# Singularitron_1B.net
KiCad netlist of a schematic drawn in EAGLE
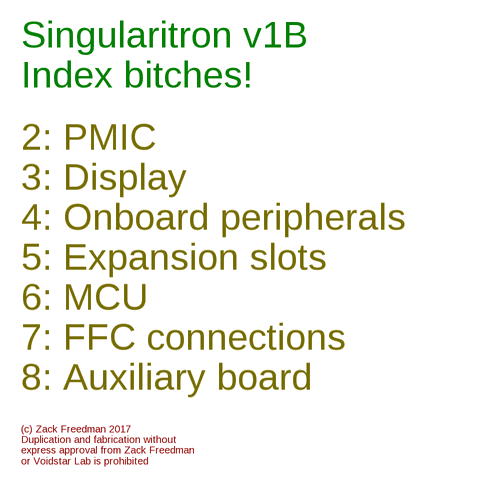
[diagram p0: schematic, sheet 1]
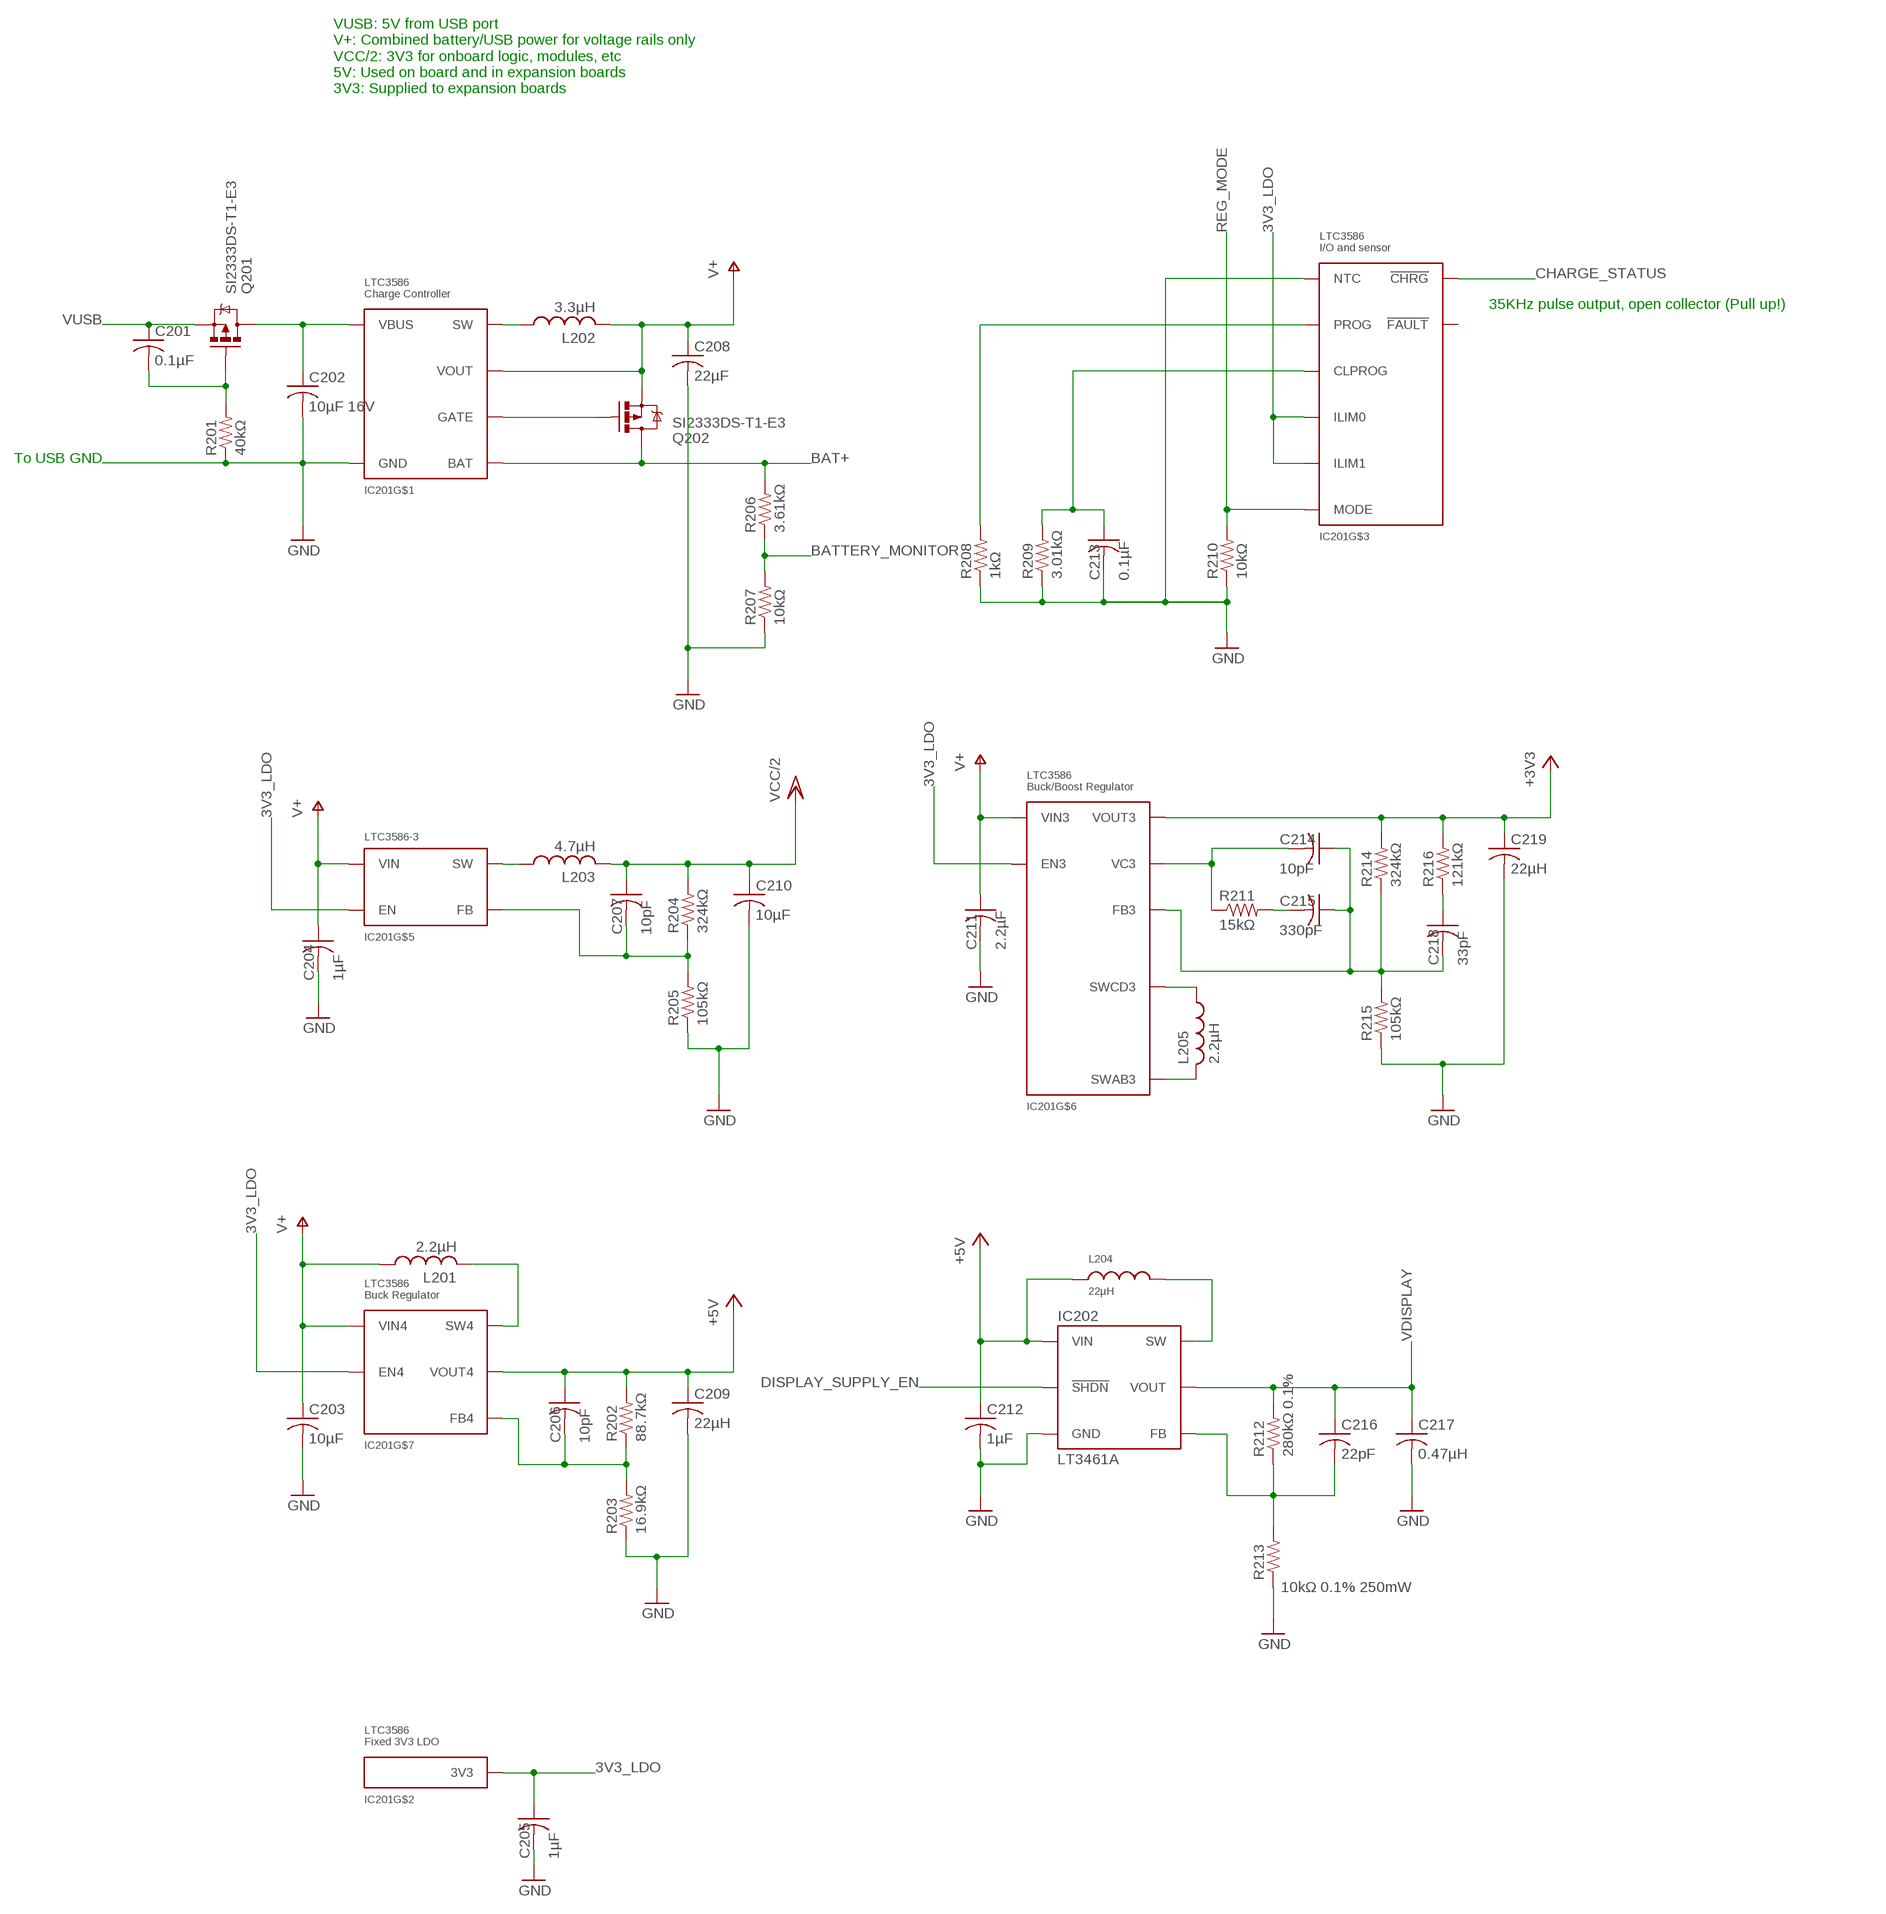
[diagram p1: schematic, sheet 2]
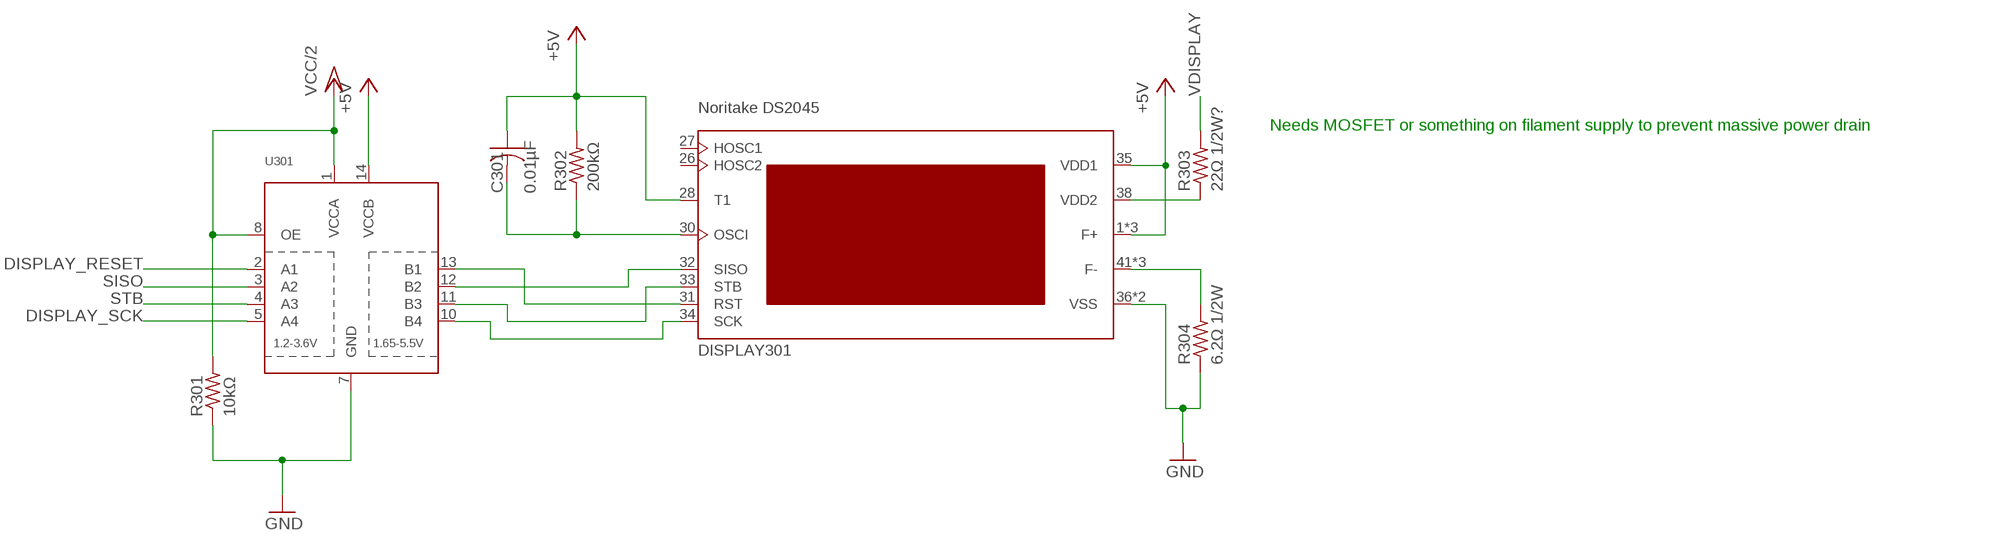
[diagram p2: schematic, sheet 3]
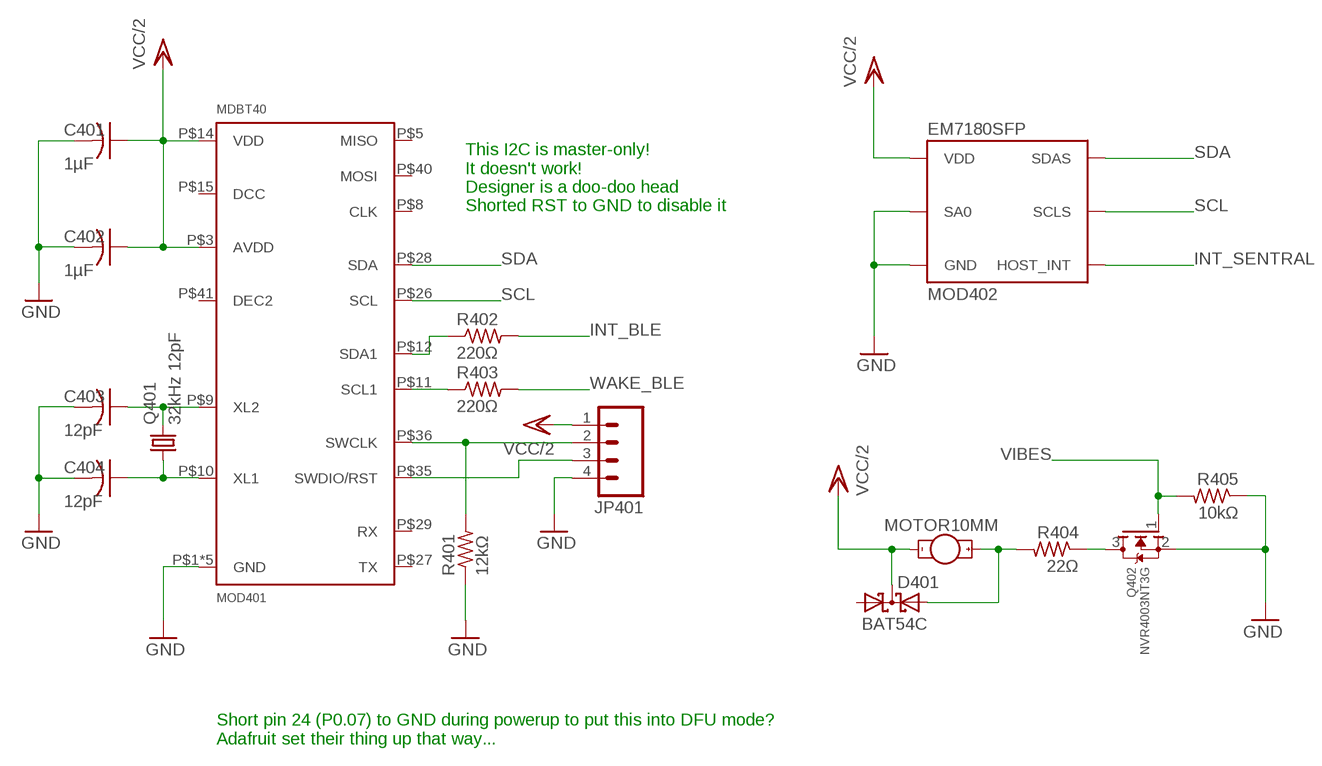
[diagram p3: schematic, sheet 4]
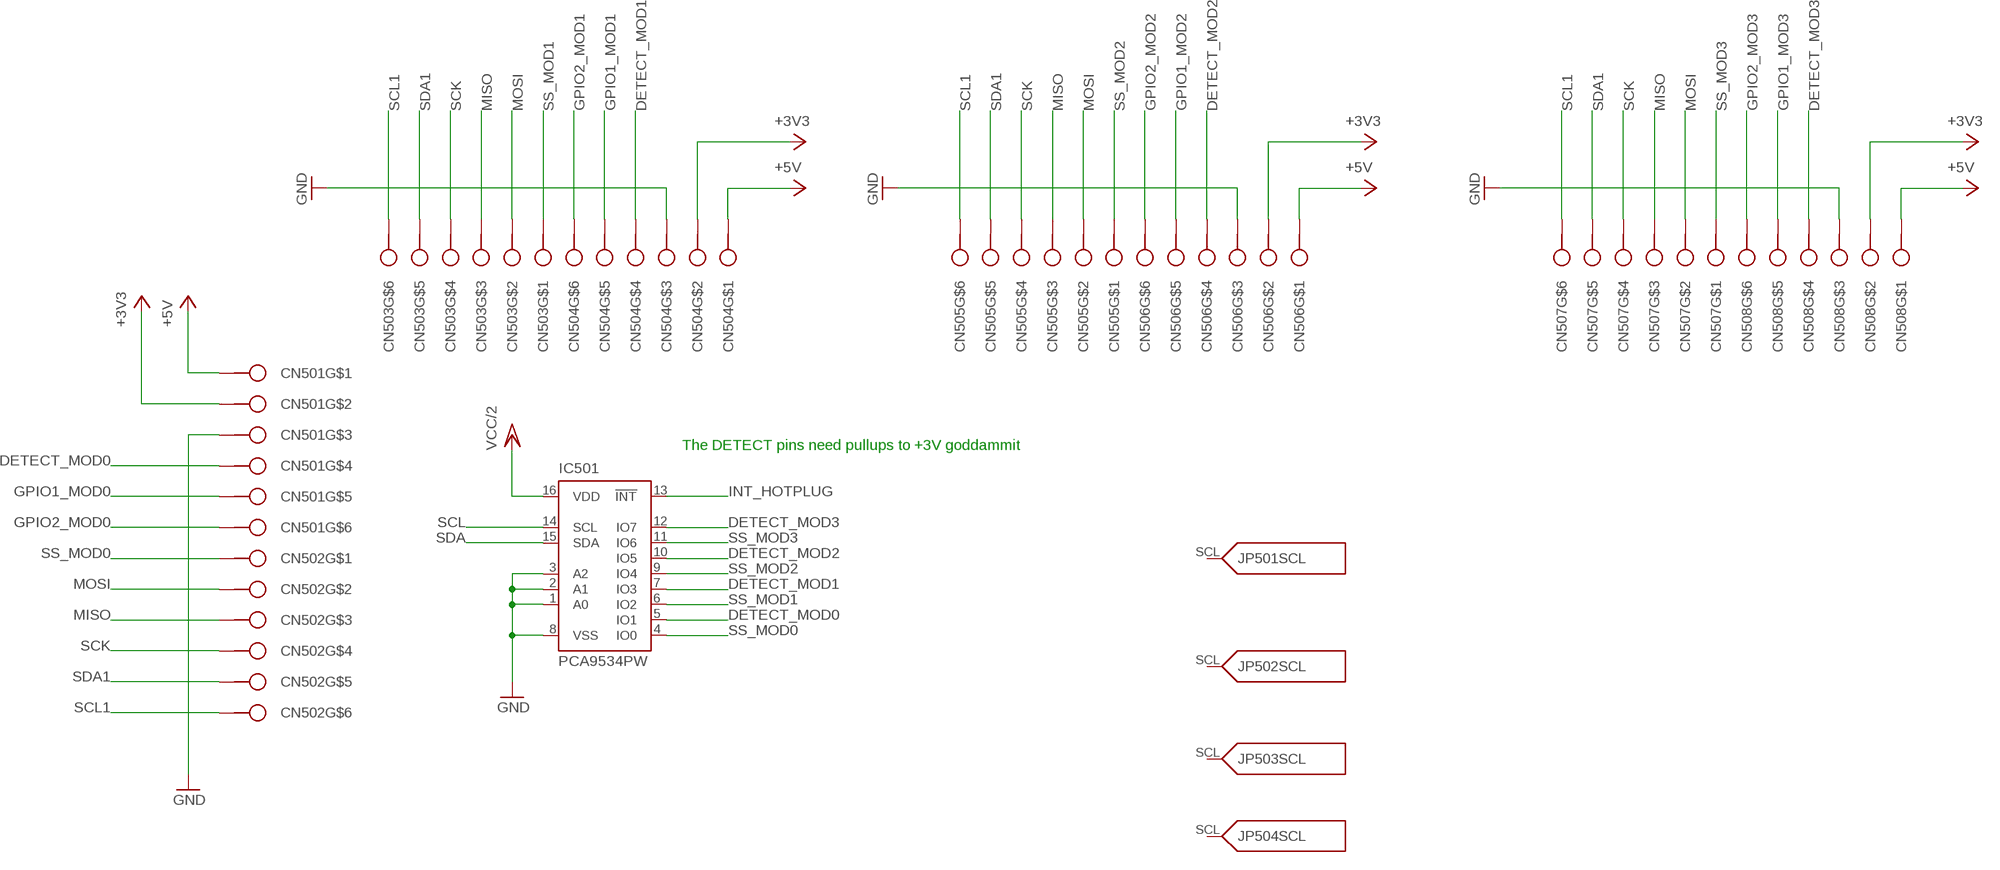
[diagram p4: schematic, sheet 5]
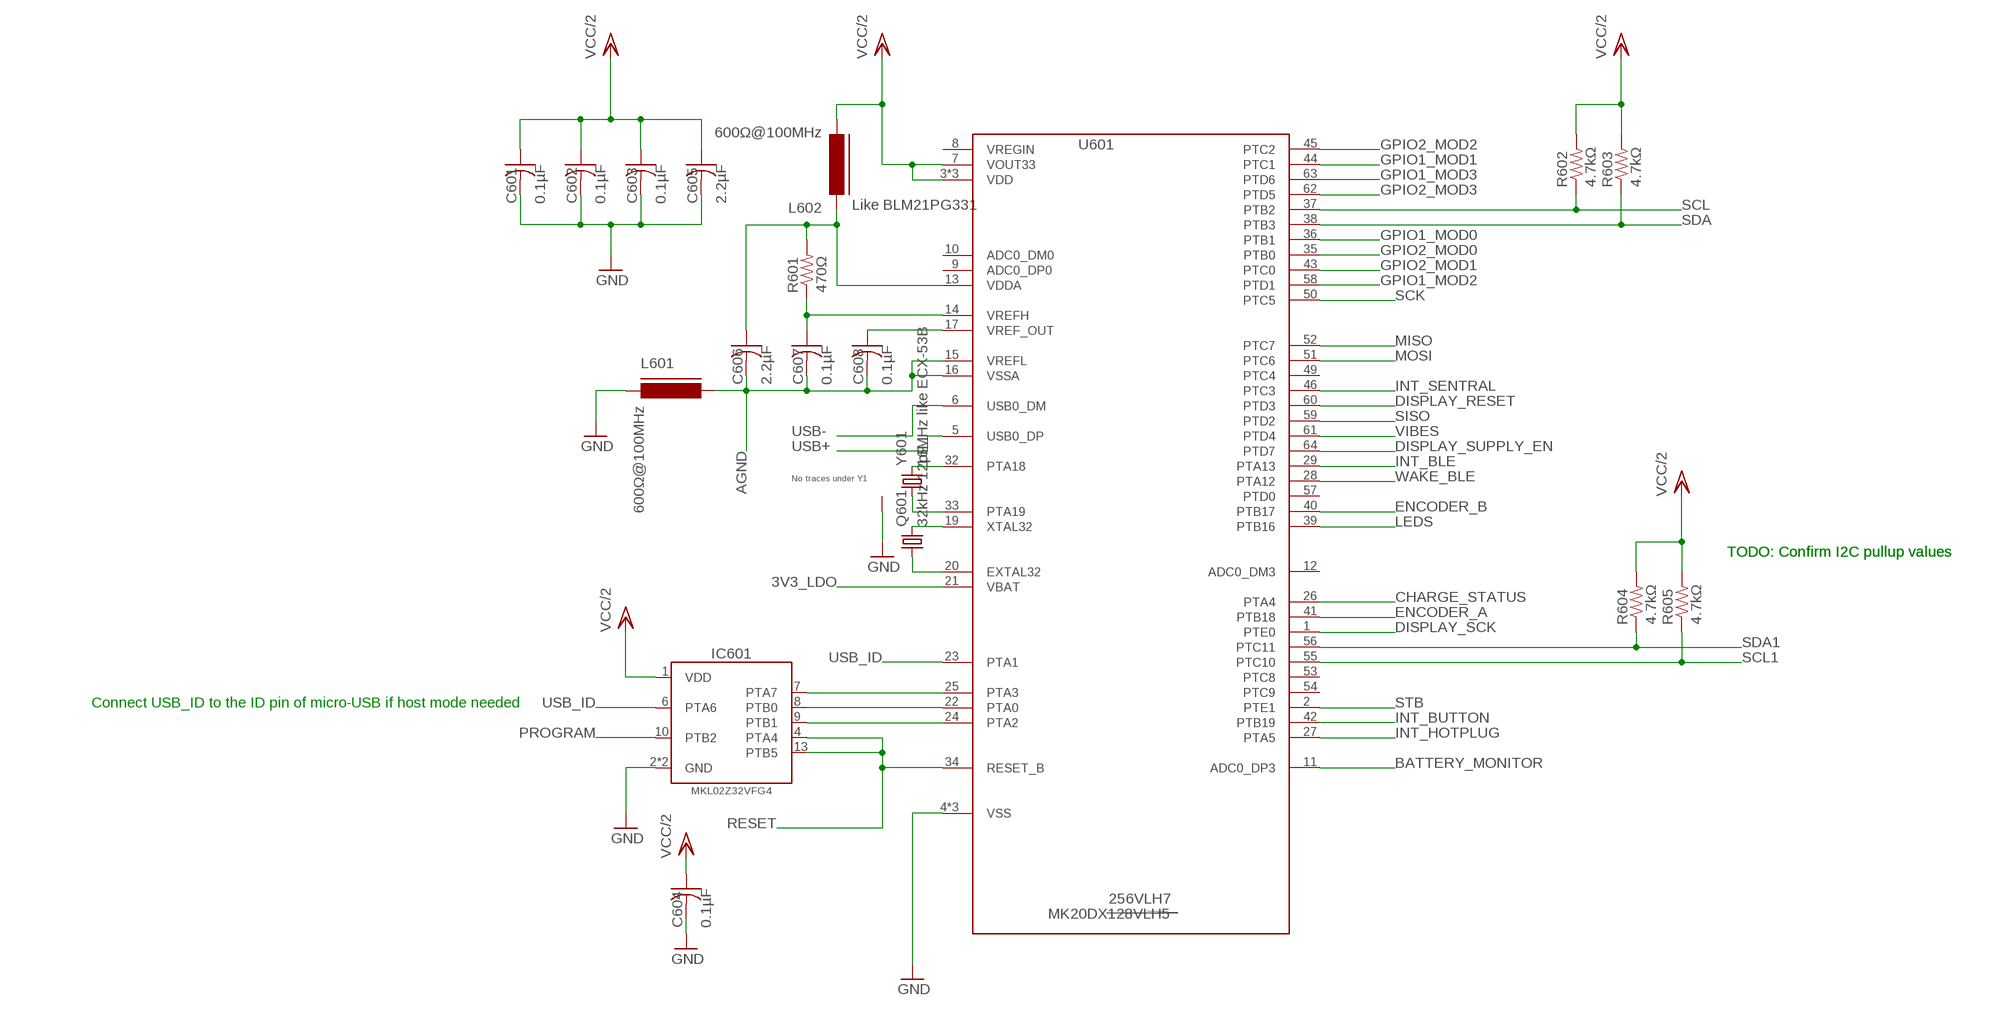
[diagram p5: schematic, sheet 6]
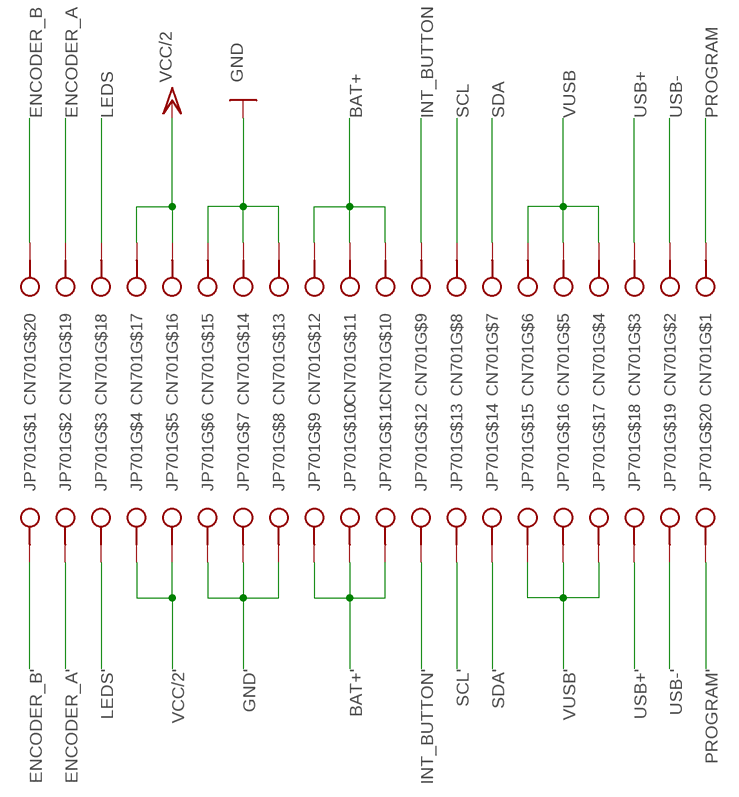
[diagram p6: schematic, sheet 7]
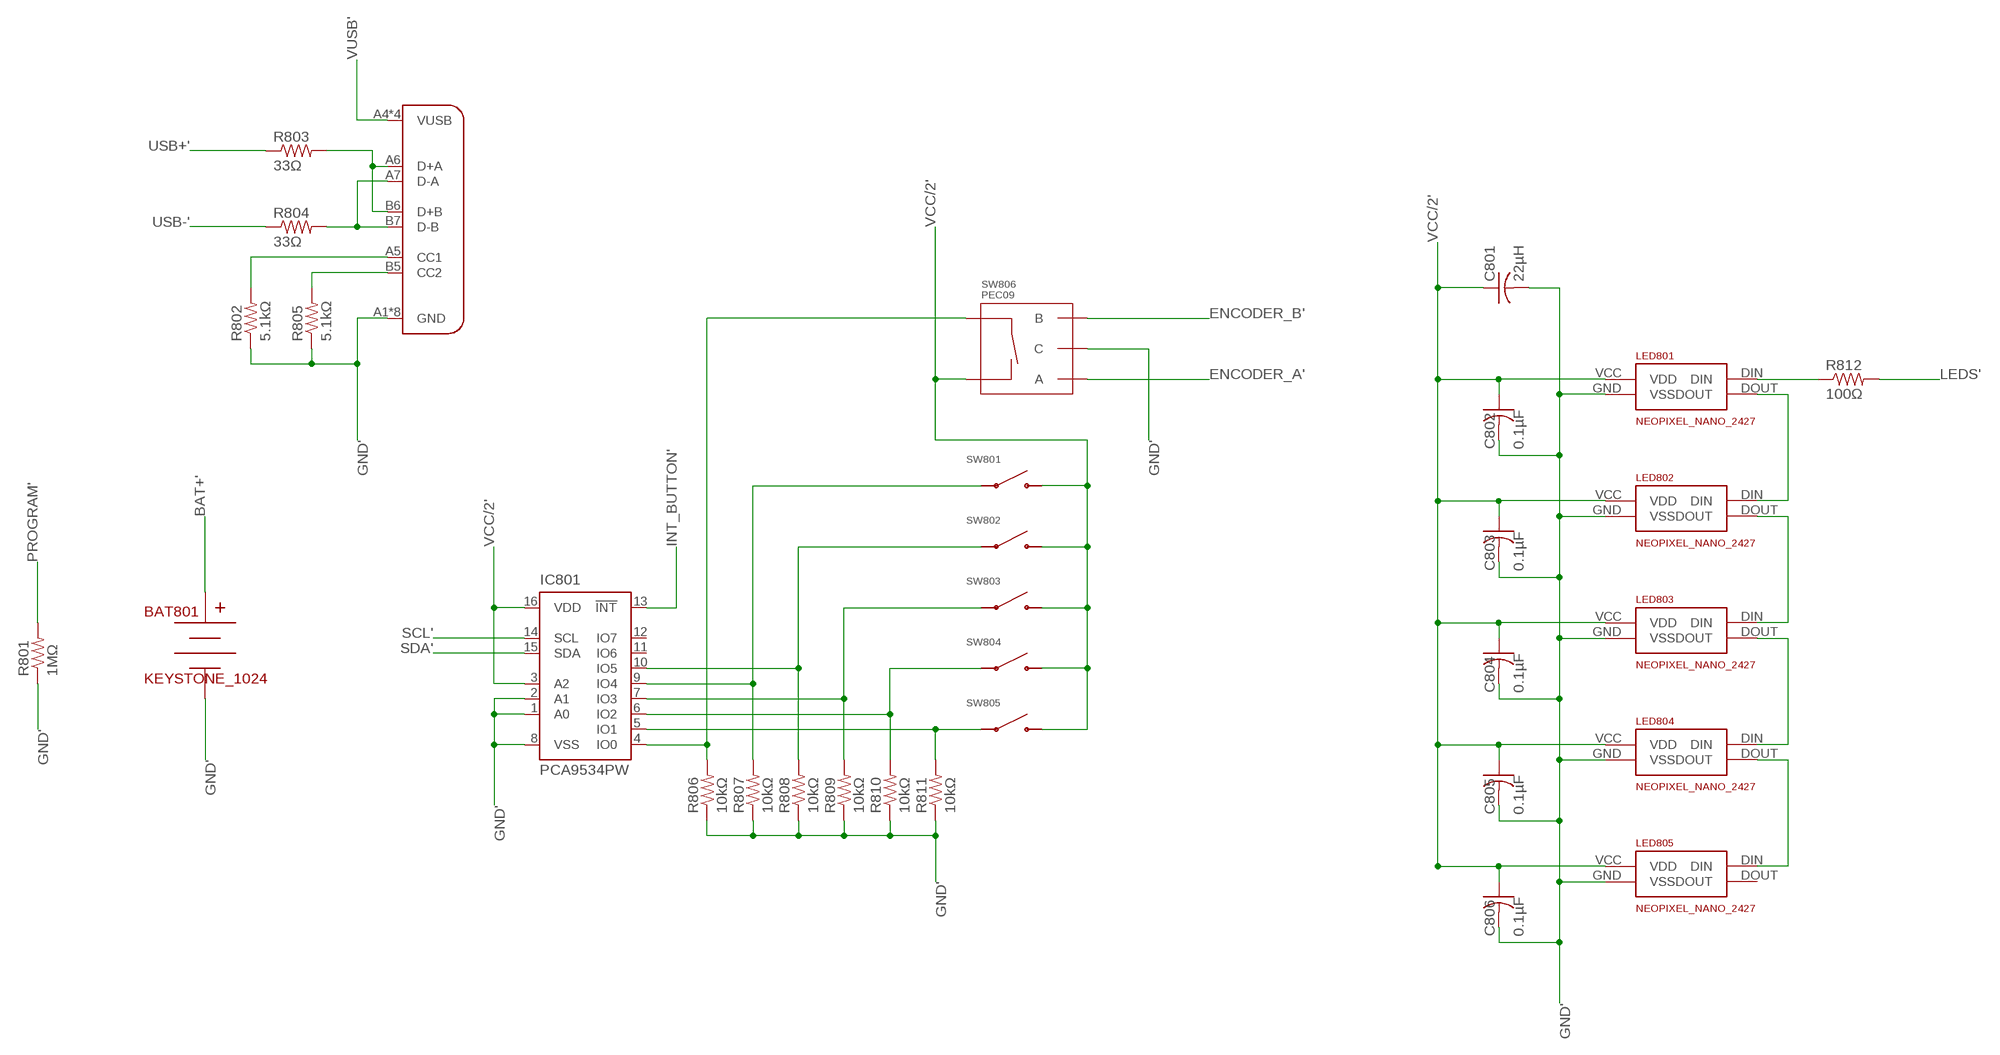
[diagram p7: schematic, sheet 8]

(export (version "E")
  (design (tool "Eeschema 10.0.6"))
  (components
    (comp (ref "C201")
      (value "0.1µF")
      (footprint "eagle-import:C0603")
      (libsource (lib "eagle-import") (part "C-USC0603"))
    )
    (comp (ref "C202")
      (value "10µF 16V")
      (footprint "eagle-import:C0805")
      (libsource (lib "eagle-import") (part "C-USC0805"))
    )
    (comp (ref "C203")
      (value "10µF")
      (footprint "eagle-import:C0805")
      (libsource (lib "eagle-import") (part "C-USC0805"))
    )
    (comp (ref "C204")
      (value "1µF")
      (footprint "eagle-import:C0603")
      (libsource (lib "eagle-import") (part "C-USC0603"))
    )
    (comp (ref "C205")
      (value "1µF")
      (footprint "eagle-import:C0603")
      (libsource (lib "eagle-import") (part "C-USC0603"))
    )
    (comp (ref "C206")
      (value "10pF")
      (footprint "eagle-import:C0603")
      (libsource (lib "eagle-import") (part "C-USC0603"))
    )
    (comp (ref "C207")
      (value "10pF")
      (footprint "eagle-import:C0603")
      (libsource (lib "eagle-import") (part "C-USC0603"))
    )
    (comp (ref "C208")
      (value "22µF")
      (footprint "eagle-import:C1210")
      (libsource (lib "eagle-import") (part "C-USC1210"))
    )
    (comp (ref "C209")
      (value "22µH")
      (footprint "eagle-import:C1210")
      (libsource (lib "eagle-import") (part "C-USC1210"))
    )
    (comp (ref "C210")
      (value "10µF")
      (footprint "eagle-import:C0805")
      (libsource (lib "eagle-import") (part "C-USC0805"))
    )
    (comp (ref "C211")
      (value "2.2µF")
      (footprint "eagle-import:C0603")
      (libsource (lib "eagle-import") (part "C-USC0603"))
    )
    (comp (ref "C212")
      (value "1µF")
      (footprint "eagle-import:C0805")
      (libsource (lib "eagle-import") (part "C-USC0805"))
    )
    (comp (ref "C213")
      (value "0.1µF")
      (footprint "eagle-import:C0603")
      (libsource (lib "eagle-import") (part "C-USC0603"))
    )
    (comp (ref "C214")
      (value "10pF")
      (footprint "eagle-import:C0603")
      (libsource (lib "eagle-import") (part "C-USC0603"))
    )
    (comp (ref "C215")
      (value "330pF")
      (footprint "eagle-import:C0603")
      (libsource (lib "eagle-import") (part "C-USC0603"))
    )
    (comp (ref "C216")
      (value "22pF")
      (footprint "eagle-import:C0805")
      (libsource (lib "eagle-import") (part "C-USC0805"))
    )
    (comp (ref "C217")
      (value "0.47µH")
      (footprint "eagle-import:C1210")
      (libsource (lib "eagle-import") (part "C-USC1210"))
    )
    (comp (ref "C218")
      (value "33pF")
      (footprint "eagle-import:C0603")
      (libsource (lib "eagle-import") (part "C-USC0603"))
    )
    (comp (ref "C219")
      (value "22µH")
      (footprint "eagle-import:C1210")
      (libsource (lib "eagle-import") (part "C-USC1210"))
    )
    (comp (ref "IC201")
      (value "LTC3586-3")
      (footprint "eagle-import:QFN-38_EP_UFE")
      (libsource (lib "eagle-import") (part "LTC3586-3"))
    )
    (comp (ref "IC202")
      (value "LT3461A")
      (footprint "eagle-import:SOT-23")
      (libsource (lib "eagle-import") (part "LT3461A"))
    )
    (comp (ref "L201")
      (value "2.2µH")
      (footprint "eagle-import:CDRH4D22_HP")
      (libsource (lib "eagle-import") (part "CDRH4D22/HP"))
    )
    (comp (ref "L202")
      (value "3.3µH")
      (footprint "eagle-import:CDRH6D12")
      (libsource (lib "eagle-import") (part "CDRH6D12"))
    )
    (comp (ref "L203")
      (value "4.7µH")
      (footprint "eagle-import:CDRH3D16_HP")
      (libsource (lib "eagle-import") (part "CDRH3D16/HP"))
    )
    (comp (ref "L204")
      (value "22µH")
      (footprint "eagle-import:CDPH4D19F")
      (libsource (lib "eagle-import") (part "SUMIDA_CDPH4D19F"))
    )
    (comp (ref "L205")
      (value "2.2µH")
      (footprint "eagle-import:CDRH4D22_HP")
      (libsource (lib "eagle-import") (part "CDRH4D22/HP"))
    )
    (comp (ref "Q201")
      (value "SI2333DS-T1-E3")
      (footprint "eagle-import:SOT23-3")
      (libsource (lib "eagle-import") (part "MOSFET-PCHANNELSMD"))
    )
    (comp (ref "Q202")
      (value "SI2333DS-T1-E3")
      (footprint "eagle-import:SOT23-3")
      (libsource (lib "eagle-import") (part "MOSFET-PCHANNELSMD"))
    )
    (comp (ref "R201")
      (value "40kΩ")
      (footprint "eagle-import:R0603")
      (libsource (lib "eagle-import") (part "R-US_R0603"))
    )
    (comp (ref "R202")
      (value "88.7kΩ")
      (footprint "eagle-import:R0603")
      (libsource (lib "eagle-import") (part "R-US_R0603"))
    )
    (comp (ref "R203")
      (value "16.9kΩ")
      (footprint "eagle-import:R0603")
      (libsource (lib "eagle-import") (part "R-US_R0603"))
    )
    (comp (ref "R204")
      (value "324kΩ")
      (footprint "eagle-import:R0603")
      (libsource (lib "eagle-import") (part "R-US_R0603"))
    )
    (comp (ref "R205")
      (value "105kΩ")
      (footprint "eagle-import:R0603")
      (libsource (lib "eagle-import") (part "R-US_R0603"))
    )
    (comp (ref "R206")
      (value "3.61kΩ")
      (footprint "eagle-import:R0603")
      (libsource (lib "eagle-import") (part "R-US_R0603"))
    )
    (comp (ref "R207")
      (value "10kΩ")
      (footprint "eagle-import:R0603")
      (libsource (lib "eagle-import") (part "R-US_R0603"))
    )
    (comp (ref "R208")
      (value "1kΩ")
      (footprint "eagle-import:R0603")
      (libsource (lib "eagle-import") (part "R-US_R0603"))
    )
    (comp (ref "R209")
      (value "3.01kΩ")
      (footprint "eagle-import:R0603")
      (libsource (lib "eagle-import") (part "R-US_R0603"))
    )
    (comp (ref "R210")
      (value "10kΩ")
      (footprint "eagle-import:R0603")
      (libsource (lib "eagle-import") (part "R-US_R0603"))
    )
    (comp (ref "R211")
      (value "15kΩ")
      (footprint "eagle-import:R0603")
      (libsource (lib "eagle-import") (part "R-US_R0603"))
    )
    (comp (ref "R212")
      (value "280kΩ 0.1%")
      (footprint "eagle-import:R0603")
      (libsource (lib "eagle-import") (part "R-US_R0603"))
    )
    (comp (ref "R213")
      (value "10kΩ 0.1% 250mW")
      (footprint "eagle-import:R0805")
      (libsource (lib "eagle-import") (part "R-US_R0805"))
    )
    (comp (ref "R214")
      (value "324kΩ")
      (footprint "eagle-import:R0603")
      (libsource (lib "eagle-import") (part "R-US_R0603"))
    )
    (comp (ref "R215")
      (value "105kΩ")
      (footprint "eagle-import:R0603")
      (libsource (lib "eagle-import") (part "R-US_R0603"))
    )
    (comp (ref "R216")
      (value "121kΩ")
      (footprint "eagle-import:R0603")
      (libsource (lib "eagle-import") (part "R-US_R0603"))
    )
    (comp (ref "C601")
      (value "0.1µF")
      (footprint "eagle-import:C0603")
      (libsource (lib "eagle-import") (part "C-USC0603"))
    )
    (comp (ref "C602")
      (value "0.1µF")
      (footprint "eagle-import:C0603")
      (libsource (lib "eagle-import") (part "C-USC0603"))
    )
    (comp (ref "C603")
      (value "0.1µF")
      (footprint "eagle-import:C0603")
      (libsource (lib "eagle-import") (part "C-USC0603"))
    )
    (comp (ref "C604")
      (value "0.1µF")
      (footprint "eagle-import:C0603")
      (libsource (lib "eagle-import") (part "C-USC0603"))
    )
    (comp (ref "C605")
      (value "2.2µF")
      (footprint "eagle-import:C0603")
      (libsource (lib "eagle-import") (part "C-USC0603"))
    )
    (comp (ref "C606")
      (value "2.2µF")
      (footprint "eagle-import:C0603")
      (libsource (lib "eagle-import") (part "C-USC0603"))
    )
    (comp (ref "C607")
      (value "0.1µF")
      (footprint "eagle-import:C0603")
      (libsource (lib "eagle-import") (part "C-USC0603"))
    )
    (comp (ref "C608")
      (value "0.1µF")
      (footprint "eagle-import:C0603")
      (libsource (lib "eagle-import") (part "C-USC0603"))
    )
    (comp (ref "IC601")
      (value "MKL02Z32VFG4")
      (footprint "eagle-import:QFN16-3X3")
      (libsource (lib "eagle-import") (part "MKL02Z32VFG4"))
    )
    (comp (ref "L601")
      (value "600Ω@100MHz")
      (footprint "eagle-import:FB603")
      (libsource (lib "eagle-import") (part "FERRITE-0603"))
    )
    (comp (ref "L602")
      (value "600Ω@100MHz")
      (footprint "eagle-import:FB603")
      (libsource (lib "eagle-import") (part "FERRITE-0603"))
    )
    (comp (ref "Q601")
      (value "32kHz 12pF")
      (footprint "eagle-import:FC-12M")
      (libsource (lib "eagle-import") (part "FC-12M"))
    )
    (comp (ref "R601")
      (value "470Ω")
      (footprint "eagle-import:R0603")
      (libsource (lib "eagle-import") (part "R-US_R0603"))
    )
    (comp (ref "R602")
      (value "4.7kΩ")
      (footprint "eagle-import:R0603")
      (libsource (lib "eagle-import") (part "R-US_R0603"))
    )
    (comp (ref "R603")
      (value "4.7kΩ")
      (footprint "eagle-import:R0603")
      (libsource (lib "eagle-import") (part "R-US_R0603"))
    )
    (comp (ref "R604")
      (value "4.7kΩ")
      (footprint "eagle-import:R0603")
      (libsource (lib "eagle-import") (part "R-US_R0603"))
    )
    (comp (ref "R605")
      (value "4.7kΩ")
      (footprint "eagle-import:R0603")
      (libsource (lib "eagle-import") (part "R-US_R0603"))
    )
    (comp (ref "U601")
      (value "MK20DX128VLH5")
      (footprint "eagle-import:MK20DX128VLH5")
      (libsource (lib "eagle-import") (part "MK20DX128VLH5"))
    )
    (comp (ref "Y601")
      (value "16MHz like ECX-53B")
      (footprint "eagle-import:CRYSTAL-SMD-5X3")
      (libsource (lib "eagle-import") (part "CRYSTAL-SHIELDED"))
    )
    (comp (ref "CN701")
      (value "HFW20R-1ST")
      (footprint "eagle-import:HFW20R-1STE1LF")
      (libsource (lib "eagle-import") (part "HFW20R-1ST"))
    )
    (comp (ref "JP701")
      (value "FFC_1MM_20POS_DIRECT")
      (footprint "eagle-import:FFC_1MM_20POS_DIRECT")
      (libsource (lib "eagle-import") (part "FFC_1MM_20POS_DIRECT"))
    )
    (comp (ref "C401")
      (value "1µF")
      (footprint "eagle-import:C0603")
      (libsource (lib "eagle-import") (part "C-USC0603"))
    )
    (comp (ref "C402")
      (value "1µF")
      (footprint "eagle-import:C0603")
      (libsource (lib "eagle-import") (part "C-USC0603"))
    )
    (comp (ref "C403")
      (value "12pF")
      (footprint "eagle-import:C0603")
      (libsource (lib "eagle-import") (part "C-USC0603"))
    )
    (comp (ref "C404")
      (value "12pF")
      (footprint "eagle-import:C0603")
      (libsource (lib "eagle-import") (part "C-USC0603"))
    )
    (comp (ref "D401")
      (value "BAT54C")
      (footprint "eagle-import:SOT23")
      (libsource (lib "eagle-import") (part "BAT54C"))
    )
    (comp (ref "JP401")
      (value "M041.27MM")
      (footprint "eagle-import:1X04-1.27MM")
      (libsource (lib "eagle-import") (part "M041.27MM"))
    )
    (comp (ref "MOD401")
      (value "MDBT40")
      (footprint "eagle-import:MDBT40")
      (libsource (lib "eagle-import") (part "MDBT40"))
    )
    (comp (ref "MOD402")
      (value "EM7180SFP")
      (footprint "eagle-import:EM7180SFP")
      (libsource (lib "eagle-import") (part "EM7180SFP"))
    )
    (comp (ref "MOTOR401")
      (value "MOTOR10MM")
      (footprint "eagle-import:VIBE-MOTOR-10MM")
      (libsource (lib "eagle-import") (part "MOTOR10MM"))
    )
    (comp (ref "Q401")
      (value "32kHz 12pF")
      (footprint "eagle-import:FC-12M")
      (libsource (lib "eagle-import") (part "FC-12M"))
    )
    (comp (ref "Q402")
      (value "NVR4003NT3G")
      (footprint "eagle-import:SOT23")
      (libsource (lib "eagle-import") (part "MOSFET-NREFLOW"))
    )
    (comp (ref "R401")
      (value "12kΩ")
      (footprint "eagle-import:R0603")
      (libsource (lib "eagle-import") (part "R-US_R0603"))
    )
    (comp (ref "R402")
      (value "220Ω")
      (footprint "eagle-import:R0603")
      (libsource (lib "eagle-import") (part "R-US_R0603"))
    )
    (comp (ref "R403")
      (value "220Ω")
      (footprint "eagle-import:R0603")
      (libsource (lib "eagle-import") (part "R-US_R0603"))
    )
    (comp (ref "R404")
      (value "22Ω")
      (footprint "eagle-import:R0603")
      (libsource (lib "eagle-import") (part "R-US_R0603"))
    )
    (comp (ref "R405")
      (value "10kΩ")
      (footprint "eagle-import:R0603")
      (libsource (lib "eagle-import") (part "R-US_R0603"))
    )
    (comp (ref "CN501")
      (value "AVX_9155066")
      (footprint "eagle-import:9155006")
      (libsource (lib "eagle-import") (part "AVX_9155066"))
    )
    (comp (ref "CN502")
      (value "AVX_9155066")
      (footprint "eagle-import:9155006")
      (libsource (lib "eagle-import") (part "AVX_9155066"))
    )
    (comp (ref "CN503")
      (value "AVX_9155066")
      (footprint "eagle-import:9155006")
      (libsource (lib "eagle-import") (part "AVX_9155066"))
    )
    (comp (ref "CN504")
      (value "AVX_9155066")
      (footprint "eagle-import:9155006")
      (libsource (lib "eagle-import") (part "AVX_9155066"))
    )
    (comp (ref "CN505")
      (value "AVX_9155066")
      (footprint "eagle-import:9155006")
      (libsource (lib "eagle-import") (part "AVX_9155066"))
    )
    (comp (ref "CN506")
      (value "AVX_9155066")
      (footprint "eagle-import:9155006")
      (libsource (lib "eagle-import") (part "AVX_9155066"))
    )
    (comp (ref "CN507")
      (value "AVX_9155066")
      (footprint "eagle-import:9155006")
      (libsource (lib "eagle-import") (part "AVX_9155066"))
    )
    (comp (ref "CN508")
      (value "AVX_9155066")
      (footprint "eagle-import:9155006")
      (libsource (lib "eagle-import") (part "AVX_9155066"))
    )
    (comp (ref "IC501")
      (value "PCA9534PW")
      (footprint "eagle-import:TSSOP16")
      (libsource (lib "eagle-import") (part "PCA9534PW"))
    )
    (comp (ref "JP501")
      (value "SINGULARITRON_CART_BASE")
      (footprint "eagle-import:SINGULARITRON_CART_BASE")
      (libsource (lib "eagle-import") (part "SINGULARITRON_CART_BASE"))
    )
    (comp (ref "JP502")
      (value "SINGULARITRON_CART_BASE")
      (footprint "eagle-import:SINGULARITRON_CART_BASE")
      (libsource (lib "eagle-import") (part "SINGULARITRON_CART_BASE"))
    )
    (comp (ref "JP503")
      (value "SINGULARITRON_CART_BASE")
      (footprint "eagle-import:SINGULARITRON_CART_BASE")
      (libsource (lib "eagle-import") (part "SINGULARITRON_CART_BASE"))
    )
    (comp (ref "JP504")
      (value "SINGULARITRON_CART_BASE")
      (footprint "eagle-import:SINGULARITRON_CART_BASE")
      (libsource (lib "eagle-import") (part "SINGULARITRON_CART_BASE"))
    )
    (comp (ref "C301")
      (value "0.01µF")
      (footprint "eagle-import:C0603")
      (libsource (lib "eagle-import") (part "C-USC0603"))
    )
    (comp (ref "DISPLAY301")
      (value "DS2045")
      (footprint "eagle-import:DS2045")
      (libsource (lib "eagle-import") (part "DS2045"))
    )
    (comp (ref "R301")
      (value "10kΩ")
      (footprint "eagle-import:R0603")
      (libsource (lib "eagle-import") (part "R-US_R0603"))
    )
    (comp (ref "R302")
      (value "200kΩ")
      (footprint "eagle-import:R0603")
      (libsource (lib "eagle-import") (part "R-US_R0603"))
    )
    (comp (ref "R303")
      (value "22Ω 1/2W?")
      (footprint "eagle-import:R0805")
      (libsource (lib "eagle-import") (part "R-US_R0805"))
    )
    (comp (ref "R304")
      (value "6.2Ω 1/2W")
      (footprint "eagle-import:R0805")
      (libsource (lib "eagle-import") (part "R-US_R0805"))
    )
    (comp (ref "U301")
      (value "TXB0104PWR")
      (footprint "eagle-import:TSSOP14")
      (libsource (lib "eagle-import") (part "TXB0104PWR"))
    )
    (comp (ref "BAT801")
      (value "KEYSTONE_1024")
      (footprint "eagle-import:KEYSTONE-1024-PROVISIONAL")
      (libsource (lib "eagle-import") (part "KEYSTONE_1024"))
    )
    (comp (ref "C801")
      (value "22µH")
      (footprint "eagle-import:C1210")
      (libsource (lib "eagle-import") (part "C-USC1210"))
    )
    (comp (ref "C802")
      (value "0.1µF")
      (footprint "eagle-import:C0603")
      (libsource (lib "eagle-import") (part "C-USC0603"))
    )
    (comp (ref "C803")
      (value "0.1µF")
      (footprint "eagle-import:C0603")
      (libsource (lib "eagle-import") (part "C-USC0603"))
    )
    (comp (ref "C804")
      (value "0.1µF")
      (footprint "eagle-import:C0603")
      (libsource (lib "eagle-import") (part "C-USC0603"))
    )
    (comp (ref "C805")
      (value "0.1µF")
      (footprint "eagle-import:C0603")
      (libsource (lib "eagle-import") (part "C-USC0603"))
    )
    (comp (ref "C806")
      (value "0.1µF")
      (footprint "eagle-import:C0603")
      (libsource (lib "eagle-import") (part "C-USC0603"))
    )
    (comp (ref "CN801")
      (value "12401548E4#2A")
      (footprint "eagle-import:12401548E4#2A")
      (libsource (lib "eagle-import") (part "12401548E4#2A"))
    )
    (comp (ref "IC801")
      (value "PCA9534PW")
      (footprint "eagle-import:TSSOP16")
      (libsource (lib "eagle-import") (part "PCA9534PW"))
    )
    (comp (ref "LED801")
      (value "NEOPIXEL_NANO_2427")
      (footprint "eagle-import:SK6805-2427")
      (libsource (lib "eagle-import") (part "NEOPIXEL_NANO_2427"))
    )
    (comp (ref "LED802")
      (value "NEOPIXEL_NANO_2427")
      (footprint "eagle-import:SK6805-2427")
      (libsource (lib "eagle-import") (part "NEOPIXEL_NANO_2427"))
    )
    (comp (ref "LED803")
      (value "NEOPIXEL_NANO_2427")
      (footprint "eagle-import:SK6805-2427")
      (libsource (lib "eagle-import") (part "NEOPIXEL_NANO_2427"))
    )
    (comp (ref "LED804")
      (value "NEOPIXEL_NANO_2427")
      (footprint "eagle-import:SK6805-2427")
      (libsource (lib "eagle-import") (part "NEOPIXEL_NANO_2427"))
    )
    (comp (ref "LED805")
      (value "NEOPIXEL_NANO_2427")
      (footprint "eagle-import:SK6805-2427")
      (libsource (lib "eagle-import") (part "NEOPIXEL_NANO_2427"))
    )
    (comp (ref "R801")
      (value "1MΩ")
      (footprint "eagle-import:R0603")
      (libsource (lib "eagle-import") (part "R-US_R0603"))
    )
    (comp (ref "R802")
      (value "5.1kΩ")
      (footprint "eagle-import:R0603")
      (libsource (lib "eagle-import") (part "R-US_R0603"))
    )
    (comp (ref "R803")
      (value "33Ω")
      (footprint "eagle-import:R0603")
      (libsource (lib "eagle-import") (part "R-US_R0603"))
    )
    (comp (ref "R804")
      (value "33Ω")
      (footprint "eagle-import:R0603")
      (libsource (lib "eagle-import") (part "R-US_R0603"))
    )
    (comp (ref "R805")
      (value "5.1kΩ")
      (footprint "eagle-import:R0603")
      (libsource (lib "eagle-import") (part "R-US_R0603"))
    )
    (comp (ref "R806")
      (value "10kΩ")
      (footprint "eagle-import:R0603")
      (libsource (lib "eagle-import") (part "R-US_R0603"))
    )
    (comp (ref "R807")
      (value "10kΩ")
      (footprint "eagle-import:R0603")
      (libsource (lib "eagle-import") (part "R-US_R0603"))
    )
    (comp (ref "R808")
      (value "10kΩ")
      (footprint "eagle-import:R0603")
      (libsource (lib "eagle-import") (part "R-US_R0603"))
    )
    (comp (ref "R809")
      (value "10kΩ")
      (footprint "eagle-import:R0603")
      (libsource (lib "eagle-import") (part "R-US_R0603"))
    )
    (comp (ref "R810")
      (value "10kΩ")
      (footprint "eagle-import:R0603")
      (libsource (lib "eagle-import") (part "R-US_R0603"))
    )
    (comp (ref "R811")
      (value "10kΩ")
      (footprint "eagle-import:R0603")
      (libsource (lib "eagle-import") (part "R-US_R0603"))
    )
    (comp (ref "R812")
      (value "100Ω")
      (footprint "eagle-import:R0603")
      (libsource (lib "eagle-import") (part "R-US_R0603"))
    )
    (comp (ref "SW801")
      (value "TACTILE_SWITCHTL3301-G")
      (footprint "eagle-import:TL3301-X-FXXX-X-G")
      (libsource (lib "eagle-import") (part "TACTILE_SWITCHTL3301-G"))
    )
    (comp (ref "SW802")
      (value "TACTILE_SWITCHTL3301-G")
      (footprint "eagle-import:TL3301-X-FXXX-X-G")
      (libsource (lib "eagle-import") (part "TACTILE_SWITCHTL3301-G"))
    )
    (comp (ref "SW803")
      (value "TACTILE_SWITCHTL3301-G")
      (footprint "eagle-import:TL3301-X-FXXX-X-G")
      (libsource (lib "eagle-import") (part "TACTILE_SWITCHTL3301-G"))
    )
    (comp (ref "SW804")
      (value "TACTILE_SWITCHTL3301-G")
      (footprint "eagle-import:TL3301-X-FXXX-X-G")
      (libsource (lib "eagle-import") (part "TACTILE_SWITCHTL3301-G"))
    )
    (comp (ref "SW805")
      (value "TACTILE_SWITCHTL3301-G")
      (footprint "eagle-import:TL3301-X-FXXX-X-G")
      (libsource (lib "eagle-import") (part "TACTILE_SWITCHTL3301-G"))
    )
    (comp (ref "SW806")
      (value "PEC09")
      (footprint "eagle-import:PEC09-2X20X-TXXXX")
      (libsource (lib "eagle-import") (part "PEC09"))
    )
  )
  (nets
    (net (code "1") (name "+3V3") (class "Default")
      (node (ref "C219") (pin "1") (pinfunction "1_1") (pintype "passive"))
      (node (ref "CN501") (pin "PAD2") (pinfunction "P$1_PAD2") (pintype "bidirectional"))
      (node (ref "CN504") (pin "PAD2") (pinfunction "P$1_PAD2") (pintype "bidirectional"))
      (node (ref "CN506") (pin "PAD2") (pinfunction "P$1_PAD2") (pintype "bidirectional"))
      (node (ref "CN508") (pin "PAD2") (pinfunction "P$1_PAD2") (pintype "bidirectional"))
      (node (ref "IC201") (pin "P$16") (pinfunction "VOUT3_P$16") (pintype "bidirectional"))
      (node (ref "IC201") (pin "P$17") (pinfunction "VOUT3_P$17") (pintype "bidirectional"))
      (node (ref "R214") (pin "2") (pinfunction "2_2") (pintype "passive"))
      (node (ref "R216") (pin "2") (pinfunction "2_2") (pintype "passive"))
    )
    (net (code "2") (name "+5V") (class "Default")
      (node (ref "C206") (pin "1") (pinfunction "1_1") (pintype "passive"))
      (node (ref "C209") (pin "1") (pinfunction "1_1") (pintype "passive"))
      (node (ref "C212") (pin "1") (pinfunction "1_1") (pintype "passive"))
      (node (ref "C301") (pin "1") (pinfunction "1_1") (pintype "passive"))
      (node (ref "CN501") (pin "PAD1") (pinfunction "P$1_PAD1") (pintype "bidirectional"))
      (node (ref "CN504") (pin "PAD1") (pinfunction "P$1_PAD1") (pintype "bidirectional"))
      (node (ref "CN506") (pin "PAD1") (pinfunction "P$1_PAD1") (pintype "bidirectional"))
      (node (ref "CN508") (pin "PAD1") (pinfunction "P$1_PAD1") (pintype "bidirectional"))
      (node (ref "DISPLAY301") (pin "1") (pinfunction "F+_1") (pintype "power_in"))
      (node (ref "DISPLAY301") (pin "2") (pinfunction "F+_2") (pintype "power_in"))
      (node (ref "DISPLAY301") (pin "28") (pinfunction "T1_28") (pintype "input"))
      (node (ref "DISPLAY301") (pin "3") (pinfunction "F+_3") (pintype "power_in"))
      (node (ref "DISPLAY301") (pin "35") (pinfunction "VDD1_35") (pintype "power_in"))
      (node (ref "IC201") (pin "P$6") (pinfunction "VOUT4_P$6") (pintype "bidirectional"))
      (node (ref "IC201") (pin "P$7") (pinfunction "VOUT4_P$7") (pintype "bidirectional"))
      (node (ref "IC202") (pin "P6") (pinfunction "VIN_P6") (pintype "bidirectional"))
      (node (ref "L204") (pin "P$1") (pinfunction "P$1_P$1") (pintype "bidirectional"))
      (node (ref "R202") (pin "2") (pinfunction "2_2") (pintype "passive"))
      (node (ref "R302") (pin "2") (pinfunction "2_2") (pintype "passive"))
      (node (ref "U301") (pin "14") (pinfunction "VCCB_14") (pintype "bidirectional"))
    )
    (net (code "3") (name "3V3_LDO") (class "Default")
      (node (ref "C205") (pin "1") (pinfunction "1_1") (pintype "passive"))
      (node (ref "IC201") (pin "P$1") (pinfunction "ILIM0_P$1") (pintype "bidirectional"))
      (node (ref "IC201") (pin "P$18") (pinfunction "EN3_P$18") (pintype "bidirectional"))
      (node (ref "IC201") (pin "P$2") (pinfunction "ILIM1_P$2") (pintype "bidirectional"))
      (node (ref "IC201") (pin "P$20") (pinfunction "EN_P$20") (pintype "bidirectional"))
      (node (ref "IC201") (pin "P$3") (pinfunction "3V3_P$3") (pintype "bidirectional"))
      (node (ref "IC201") (pin "P$33") (pinfunction "EN4_P$33") (pintype "bidirectional"))
      (node (ref "U601") (pin "21") (pinfunction "VBAT_21") (pintype "bidirectional"))
    )
    (net (code "4") (name "AGND") (class "Default")
      (node (ref "C606") (pin "2") (pinfunction "2_2") (pintype "passive"))
      (node (ref "C607") (pin "2") (pinfunction "2_2") (pintype "passive"))
      (node (ref "C608") (pin "2") (pinfunction "2_2") (pintype "passive"))
      (node (ref "L601") (pin "1") (pinfunction "1_1") (pintype "passive"))
      (node (ref "U601") (pin "15") (pinfunction "VREFL_15") (pintype "bidirectional"))
      (node (ref "U601") (pin "16") (pinfunction "VSSA_16") (pintype "bidirectional"))
    )
    (net (code "5") (name "BAT+") (class "Default")
      (node (ref "CN701") (pin "P$10") (pinfunction "P$1_P$10") (pintype "bidirectional"))
      (node (ref "CN701") (pin "P$11") (pinfunction "P$1_P$11") (pintype "bidirectional"))
      (node (ref "CN701") (pin "P$12") (pinfunction "P$1_P$12") (pintype "bidirectional"))
      (node (ref "IC201") (pin "P$32") (pinfunction "BAT_P$32") (pintype "bidirectional"))
      (node (ref "Q202") (pin "3") (pinfunction "D_3") (pintype "passive"))
      (node (ref "R206") (pin "2") (pinfunction "2_2") (pintype "passive"))
    )
    (net (code "6") (name "BAT+'") (class "Default")
      (node (ref "BAT801") (pin "+") (pinfunction "V+_+") (pintype "bidirectional"))
      (node (ref "JP701") (pin "P$10") (pinfunction "P$1_P$10") (pintype "bidirectional"))
      (node (ref "JP701") (pin "P$11") (pinfunction "P$1_P$11") (pintype "bidirectional"))
      (node (ref "JP701") (pin "P$9") (pinfunction "P$1_P$9") (pintype "bidirectional"))
    )
    (net (code "7") (name "BATTERY_MONITOR") (class "Default")
      (node (ref "R206") (pin "1") (pinfunction "1_1") (pintype "passive"))
      (node (ref "R207") (pin "2") (pinfunction "2_2") (pintype "passive"))
      (node (ref "U601") (pin "11") (pinfunction "ADC0_DP3_11") (pintype "bidirectional"))
    )
    (net (code "8") (name "CHARGE_STATUS") (class "Default")
      (node (ref "IC201") (pin "P$30") (pinfunction "~{CHRG}_P$30") (pintype "bidirectional"))
      (node (ref "U601") (pin "26") (pinfunction "PTA4_26") (pintype "bidirectional"))
    )
    (net (code "9") (name "DETECT_MOD0") (class "Default")
      (node (ref "CN501") (pin "PAD4") (pinfunction "P$1_PAD4") (pintype "bidirectional"))
      (node (ref "IC501") (pin "5") (pinfunction "IO1_5") (pintype "bidirectional"))
    )
    (net (code "10") (name "DETECT_MOD1") (class "Default")
      (node (ref "CN504") (pin "PAD4") (pinfunction "P$1_PAD4") (pintype "bidirectional"))
      (node (ref "IC501") (pin "7") (pinfunction "IO3_7") (pintype "bidirectional"))
    )
    (net (code "11") (name "DETECT_MOD2") (class "Default")
      (node (ref "CN506") (pin "PAD4") (pinfunction "P$1_PAD4") (pintype "bidirectional"))
      (node (ref "IC501") (pin "10") (pinfunction "IO5_10") (pintype "bidirectional"))
    )
    (net (code "12") (name "DETECT_MOD3") (class "Default")
      (node (ref "CN508") (pin "PAD4") (pinfunction "P$1_PAD4") (pintype "bidirectional"))
      (node (ref "IC501") (pin "12") (pinfunction "IO7_12") (pintype "bidirectional"))
    )
    (net (code "13") (name "DISPLAY_RESET") (class "Default")
      (node (ref "U301") (pin "2") (pinfunction "A1_2") (pintype "bidirectional"))
      (node (ref "U601") (pin "60") (pinfunction "PTD3_60") (pintype "bidirectional"))
    )
    (net (code "14") (name "DISPLAY_SCK") (class "Default")
      (node (ref "U301") (pin "5") (pinfunction "A4_5") (pintype "bidirectional"))
      (node (ref "U601") (pin "1") (pinfunction "PTE0_1") (pintype "bidirectional"))
    )
    (net (code "15") (name "DISPLAY_SUPPLY_EN") (class "Default")
      (node (ref "IC202") (pin "P4") (pinfunction "~{SHDN}_P4") (pintype "bidirectional"))
      (node (ref "U601") (pin "64") (pinfunction "PTD7_64") (pintype "bidirectional"))
    )
    (net (code "16") (name "ENCODER_A") (class "Default")
      (node (ref "CN701") (pin "P$19") (pinfunction "P$1_P$19") (pintype "bidirectional"))
      (node (ref "U601") (pin "41") (pinfunction "PTB18_41") (pintype "bidirectional"))
    )
    (net (code "17") (name "ENCODER_A'") (class "Default")
      (node (ref "JP701") (pin "P$2") (pinfunction "P$1_P$2") (pintype "bidirectional"))
      (node (ref "SW806") (pin "A") (pinfunction "A_A") (pintype "bidirectional"))
    )
    (net (code "18") (name "ENCODER_B") (class "Default")
      (node (ref "CN701") (pin "P$20") (pinfunction "P$1_P$20") (pintype "bidirectional"))
      (node (ref "U601") (pin "40") (pinfunction "PTB17_40") (pintype "bidirectional"))
    )
    (net (code "19") (name "ENCODER_B'") (class "Default")
      (node (ref "JP701") (pin "P$1") (pinfunction "P$1_P$1") (pintype "bidirectional"))
      (node (ref "SW806") (pin "B") (pinfunction "B_B") (pintype "bidirectional"))
    )
    (net (code "20") (name "GND") (class "Default")
      (node (ref "C202") (pin "2") (pinfunction "2_2") (pintype "passive"))
      (node (ref "C203") (pin "2") (pinfunction "2_2") (pintype "passive"))
      (node (ref "C204") (pin "2") (pinfunction "2_2") (pintype "passive"))
      (node (ref "C205") (pin "2") (pinfunction "2_2") (pintype "passive"))
      (node (ref "C208") (pin "2") (pinfunction "2_2") (pintype "passive"))
      (node (ref "C209") (pin "2") (pinfunction "2_2") (pintype "passive"))
      (node (ref "C210") (pin "2") (pinfunction "2_2") (pintype "passive"))
      (node (ref "C211") (pin "2") (pinfunction "2_2") (pintype "passive"))
      (node (ref "C212") (pin "2") (pinfunction "2_2") (pintype "passive"))
      (node (ref "C213") (pin "2") (pinfunction "2_2") (pintype "passive"))
      (node (ref "C217") (pin "2") (pinfunction "2_2") (pintype "passive"))
      (node (ref "C219") (pin "2") (pinfunction "2_2") (pintype "passive"))
      (node (ref "C401") (pin "2") (pinfunction "2_2") (pintype "passive"))
      (node (ref "C402") (pin "2") (pinfunction "2_2") (pintype "passive"))
      (node (ref "C403") (pin "2") (pinfunction "2_2") (pintype "passive"))
      (node (ref "C404") (pin "2") (pinfunction "2_2") (pintype "passive"))
      (node (ref "C601") (pin "2") (pinfunction "2_2") (pintype "passive"))
      (node (ref "C602") (pin "2") (pinfunction "2_2") (pintype "passive"))
      (node (ref "C603") (pin "2") (pinfunction "2_2") (pintype "passive"))
      (node (ref "C604") (pin "2") (pinfunction "2_2") (pintype "passive"))
      (node (ref "C605") (pin "2") (pinfunction "2_2") (pintype "passive"))
      (node (ref "CN501") (pin "PAD3") (pinfunction "P$1_PAD3") (pintype "bidirectional"))
      (node (ref "CN504") (pin "PAD3") (pinfunction "P$1_PAD3") (pintype "bidirectional"))
      (node (ref "CN506") (pin "PAD3") (pinfunction "P$1_PAD3") (pintype "bidirectional"))
      (node (ref "CN508") (pin "PAD3") (pinfunction "P$1_PAD3") (pintype "bidirectional"))
      (node (ref "CN701") (pin "P$13") (pinfunction "P$1_P$13") (pintype "bidirectional"))
      (node (ref "CN701") (pin "P$14") (pinfunction "P$1_P$14") (pintype "bidirectional"))
      (node (ref "CN701") (pin "P$15") (pinfunction "P$1_P$15") (pintype "bidirectional"))
      (node (ref "DISPLAY301") (pin "36") (pinfunction "VSS_36") (pintype "power_in"))
      (node (ref "DISPLAY301") (pin "37") (pinfunction "VSS_37") (pintype "power_in"))
      (node (ref "IC201") (pin "EP") (pinfunction "GND_EP") (pintype "bidirectional"))
      (node (ref "IC201") (pin "P$5") (pinfunction "NTC_P$5") (pintype "bidirectional"))
      (node (ref "IC202") (pin "P2") (pinfunction "GND_P2") (pintype "bidirectional"))
      (node (ref "IC501") (pin "1") (pinfunction "A0_1") (pintype "input"))
      (node (ref "IC501") (pin "2") (pinfunction "A1_2") (pintype "input"))
      (node (ref "IC501") (pin "3") (pinfunction "A2_3") (pintype "input"))
      (node (ref "IC501") (pin "8") (pinfunction "VSS_8") (pintype "power_in"))
      (node (ref "IC601") (pin "2") (pinfunction "GND_2") (pintype "bidirectional"))
      (node (ref "IC601") (pin "PAD") (pinfunction "GND_PAD") (pintype "bidirectional"))
      (node (ref "JP401") (pin "4") (pinfunction "4_4") (pintype "passive"))
      (node (ref "L601") (pin "2") (pinfunction "2_2") (pintype "passive"))
      (node (ref "MOD401") (pin "P$1") (pinfunction "GND_P$1") (pintype "bidirectional"))
      (node (ref "MOD401") (pin "P$13") (pinfunction "GND_P$13") (pintype "bidirectional"))
      (node (ref "MOD401") (pin "P$2") (pinfunction "GND_P$2") (pintype "bidirectional"))
      (node (ref "MOD401") (pin "P$25") (pinfunction "GND_P$25") (pintype "bidirectional"))
      (node (ref "MOD401") (pin "P$42") (pinfunction "GND_P$42") (pintype "bidirectional"))
      (node (ref "MOD402") (pin "P$5") (pinfunction "SA0_P$5") (pintype "bidirectional"))
      (node (ref "MOD402") (pin "P$6") (pinfunction "GND_P$6") (pintype "bidirectional"))
      (node (ref "Q402") (pin "2") (pinfunction "S_2") (pintype "bidirectional"))
      (node (ref "R201") (pin "1") (pinfunction "1_1") (pintype "passive"))
      (node (ref "R203") (pin "1") (pinfunction "1_1") (pintype "passive"))
      (node (ref "R205") (pin "1") (pinfunction "1_1") (pintype "passive"))
      (node (ref "R207") (pin "1") (pinfunction "1_1") (pintype "passive"))
      (node (ref "R208") (pin "1") (pinfunction "1_1") (pintype "passive"))
      (node (ref "R209") (pin "1") (pinfunction "1_1") (pintype "passive"))
      (node (ref "R210") (pin "1") (pinfunction "1_1") (pintype "passive"))
      (node (ref "R213") (pin "1") (pinfunction "1_1") (pintype "passive"))
      (node (ref "R215") (pin "1") (pinfunction "1_1") (pintype "passive"))
      (node (ref "R301") (pin "1") (pinfunction "1_1") (pintype "passive"))
      (node (ref "R304") (pin "1") (pinfunction "1_1") (pintype "passive"))
      (node (ref "R401") (pin "1") (pinfunction "1_1") (pintype "passive"))
      (node (ref "R405") (pin "1") (pinfunction "1_1") (pintype "passive"))
      (node (ref "U301") (pin "7") (pinfunction "GND_7") (pintype "bidirectional"))
      (node (ref "U601") (pin "31") (pinfunction "VSS_31") (pintype "bidirectional"))
      (node (ref "U601") (pin "4") (pinfunction "VSS_4") (pintype "bidirectional"))
      (node (ref "U601") (pin "47") (pinfunction "VSS_47") (pintype "bidirectional"))
      (node (ref "Y601") (pin "2") (pinfunction "SHIELD_2") (pintype "bidirectional"))
      (node (ref "Y601") (pin "4") (pinfunction "SHIELD_4") (pintype "bidirectional"))
    )
    (net (code "21") (name "GND'") (class "Default")
      (node (ref "BAT801") (pin "-") (pinfunction "V-_-") (pintype "bidirectional"))
      (node (ref "C801") (pin "2") (pinfunction "2_2") (pintype "passive"))
      (node (ref "C802") (pin "2") (pinfunction "2_2") (pintype "passive"))
      (node (ref "C803") (pin "2") (pinfunction "2_2") (pintype "passive"))
      (node (ref "C804") (pin "2") (pinfunction "2_2") (pintype "passive"))
      (node (ref "C805") (pin "2") (pinfunction "2_2") (pintype "passive"))
      (node (ref "C806") (pin "2") (pinfunction "2_2") (pintype "passive"))
      (node (ref "CN801") (pin "A1") (pinfunction "GND_A1") (pintype "bidirectional"))
      (node (ref "CN801") (pin "A12") (pinfunction "GND_A12") (pintype "bidirectional"))
      (node (ref "CN801") (pin "B1") (pinfunction "GND_B1") (pintype "bidirectional"))
      (node (ref "CN801") (pin "B12") (pinfunction "GND_B12") (pintype "bidirectional"))
      (node (ref "CN801") (pin "SHIELD1") (pinfunction "GND_SHIELD1") (pintype "bidirectional"))
      (node (ref "CN801") (pin "SHIELD2") (pinfunction "GND_SHIELD2") (pintype "bidirectional"))
      (node (ref "CN801") (pin "SHIELD3") (pinfunction "GND_SHIELD3") (pintype "bidirectional"))
      (node (ref "CN801") (pin "SHIELD4") (pinfunction "GND_SHIELD4") (pintype "bidirectional"))
      (node (ref "IC801") (pin "1") (pinfunction "A0_1") (pintype "input"))
      (node (ref "IC801") (pin "2") (pinfunction "A1_2") (pintype "input"))
      (node (ref "IC801") (pin "8") (pinfunction "VSS_8") (pintype "power_in"))
      (node (ref "JP701") (pin "P$6") (pinfunction "P$1_P$6") (pintype "bidirectional"))
      (node (ref "JP701") (pin "P$7") (pinfunction "P$1_P$7") (pintype "bidirectional"))
      (node (ref "JP701") (pin "P$8") (pinfunction "P$1_P$8") (pintype "bidirectional"))
      (node (ref "LED801") (pin "GND") (pinfunction "VSS_GND") (pintype "bidirectional"))
      (node (ref "LED802") (pin "GND") (pinfunction "VSS_GND") (pintype "bidirectional"))
      (node (ref "LED803") (pin "GND") (pinfunction "VSS_GND") (pintype "bidirectional"))
      (node (ref "LED804") (pin "GND") (pinfunction "VSS_GND") (pintype "bidirectional"))
      (node (ref "LED805") (pin "GND") (pinfunction "VSS_GND") (pintype "bidirectional"))
      (node (ref "R801") (pin "1") (pinfunction "1_1") (pintype "passive"))
      (node (ref "R802") (pin "1") (pinfunction "1_1") (pintype "passive"))
      (node (ref "R805") (pin "1") (pinfunction "1_1") (pintype "passive"))
      (node (ref "R806") (pin "1") (pinfunction "1_1") (pintype "passive"))
      (node (ref "R807") (pin "1") (pinfunction "1_1") (pintype "passive"))
      (node (ref "R808") (pin "1") (pinfunction "1_1") (pintype "passive"))
      (node (ref "R809") (pin "1") (pinfunction "1_1") (pintype "passive"))
      (node (ref "R810") (pin "1") (pinfunction "1_1") (pintype "passive"))
      (node (ref "R811") (pin "1") (pinfunction "1_1") (pintype "passive"))
      (node (ref "SW806") (pin "C") (pinfunction "C_C") (pintype "bidirectional"))
    )
    (net (code "22") (name "GPIO1_MOD0") (class "Default")
      (node (ref "CN501") (pin "PAD5") (pinfunction "P$1_PAD5") (pintype "bidirectional"))
      (node (ref "U601") (pin "36") (pinfunction "PTB1_36") (pintype "bidirectional"))
    )
    (net (code "23") (name "GPIO1_MOD1") (class "Default")
      (node (ref "CN504") (pin "PAD5") (pinfunction "P$1_PAD5") (pintype "bidirectional"))
      (node (ref "U601") (pin "44") (pinfunction "PTC1_44") (pintype "bidirectional"))
    )
    (net (code "24") (name "GPIO1_MOD2") (class "Default")
      (node (ref "CN506") (pin "PAD5") (pinfunction "P$1_PAD5") (pintype "bidirectional"))
      (node (ref "U601") (pin "58") (pinfunction "PTD1_58") (pintype "bidirectional"))
    )
    (net (code "25") (name "GPIO1_MOD3") (class "Default")
      (node (ref "CN508") (pin "PAD5") (pinfunction "P$1_PAD5") (pintype "bidirectional"))
      (node (ref "U601") (pin "63") (pinfunction "PTD6_63") (pintype "bidirectional"))
    )
    (net (code "26") (name "GPIO2_MOD0") (class "Default")
      (node (ref "CN501") (pin "PAD6") (pinfunction "P$1_PAD6") (pintype "bidirectional"))
      (node (ref "U601") (pin "35") (pinfunction "PTB0_35") (pintype "bidirectional"))
    )
    (net (code "27") (name "GPIO2_MOD1") (class "Default")
      (node (ref "CN504") (pin "PAD6") (pinfunction "P$1_PAD6") (pintype "bidirectional"))
      (node (ref "U601") (pin "43") (pinfunction "PTC0_43") (pintype "bidirectional"))
    )
    (net (code "28") (name "GPIO2_MOD2") (class "Default")
      (node (ref "CN506") (pin "PAD6") (pinfunction "P$1_PAD6") (pintype "bidirectional"))
      (node (ref "U601") (pin "45") (pinfunction "PTC2_45") (pintype "bidirectional"))
    )
    (net (code "29") (name "GPIO2_MOD3") (class "Default")
      (node (ref "CN508") (pin "PAD6") (pinfunction "P$1_PAD6") (pintype "bidirectional"))
      (node (ref "U601") (pin "62") (pinfunction "PTD5_62") (pintype "bidirectional"))
    )
    (net (code "30") (name "INT_BLE") (class "Default")
      (node (ref "R402") (pin "2") (pinfunction "2_2") (pintype "passive"))
      (node (ref "U601") (pin "29") (pinfunction "PTA13_29") (pintype "bidirectional"))
    )
    (net (code "31") (name "INT_BUTTON") (class "Default")
      (node (ref "CN701") (pin "P$9") (pinfunction "P$1_P$9") (pintype "bidirectional"))
      (node (ref "U601") (pin "42") (pinfunction "PTB19_42") (pintype "bidirectional"))
    )
    (net (code "32") (name "INT_BUTTON'") (class "Default")
      (node (ref "IC801") (pin "13") (pinfunction "~{INT}_13") (pintype "open_collector"))
      (node (ref "JP701") (pin "P$12") (pinfunction "P$1_P$12") (pintype "bidirectional"))
    )
    (net (code "33") (name "INT_HOTPLUG") (class "Default")
      (node (ref "IC501") (pin "13") (pinfunction "~{INT}_13") (pintype "open_collector"))
      (node (ref "U601") (pin "27") (pinfunction "PTA5_27") (pintype "bidirectional"))
    )
    (net (code "34") (name "INT_SENTRAL") (class "Default")
      (node (ref "MOD402") (pin "P$4") (pinfunction "HOST_INT_P$4") (pintype "bidirectional"))
      (node (ref "U601") (pin "46") (pinfunction "PTC3_46") (pintype "bidirectional"))
    )
    (net (code "35") (name "LEDS") (class "Default")
      (node (ref "CN701") (pin "P$18") (pinfunction "P$1_P$18") (pintype "bidirectional"))
      (node (ref "U601") (pin "39") (pinfunction "PTB16_39") (pintype "bidirectional"))
    )
    (net (code "36") (name "LEDS'") (class "Default")
      (node (ref "JP701") (pin "P$3") (pinfunction "P$1_P$3") (pintype "bidirectional"))
      (node (ref "R812") (pin "2") (pinfunction "2_2") (pintype "passive"))
    )
    (net (code "37") (name "MISO") (class "Default")
      (node (ref "CN502") (pin "PAD3") (pinfunction "P$1_PAD3") (pintype "bidirectional"))
      (node (ref "CN503") (pin "PAD3") (pinfunction "P$1_PAD3") (pintype "bidirectional"))
      (node (ref "CN505") (pin "PAD3") (pinfunction "P$1_PAD3") (pintype "bidirectional"))
      (node (ref "CN507") (pin "PAD3") (pinfunction "P$1_PAD3") (pintype "bidirectional"))
      (node (ref "U601") (pin "52") (pinfunction "PTC7_52") (pintype "bidirectional"))
    )
    (net (code "38") (name "MOSI") (class "Default")
      (node (ref "CN502") (pin "PAD2") (pinfunction "P$1_PAD2") (pintype "bidirectional"))
      (node (ref "CN503") (pin "PAD2") (pinfunction "P$1_PAD2") (pintype "bidirectional"))
      (node (ref "CN505") (pin "PAD2") (pinfunction "P$1_PAD2") (pintype "bidirectional"))
      (node (ref "CN507") (pin "PAD2") (pinfunction "P$1_PAD2") (pintype "bidirectional"))
      (node (ref "U601") (pin "51") (pinfunction "PTC6_51") (pintype "bidirectional"))
    )
    (net (code "39") (name "Net-(C215-Pad2)") (class "Default")
      (node (ref "C215") (pin "2") (pinfunction "2_2") (pintype "passive"))
      (node (ref "R211") (pin "2") (pinfunction "2_2") (pintype "passive"))
    )
    (net (code "40") (name "Net-(C218-Pad1)") (class "Default")
      (node (ref "C218") (pin "1") (pinfunction "1_1") (pintype "passive"))
      (node (ref "R216") (pin "1") (pinfunction "1_1") (pintype "passive"))
    )
    (net (code "41") (name "Net-(CN801-CC1)") (class "Default")
      (node (ref "CN801") (pin "A5") (pinfunction "CC1_A5") (pintype "bidirectional"))
      (node (ref "R802") (pin "2") (pinfunction "2_2") (pintype "passive"))
    )
    (net (code "42") (name "Net-(CN801-CC2)") (class "Default")
      (node (ref "CN801") (pin "B5") (pinfunction "CC2_B5") (pintype "bidirectional"))
      (node (ref "R805") (pin "2") (pinfunction "2_2") (pintype "passive"))
    )
    (net (code "43") (name "Net-(CN801-D+A)") (class "Default")
      (node (ref "CN801") (pin "A6") (pinfunction "D+A_A6") (pintype "bidirectional"))
      (node (ref "CN801") (pin "B6") (pinfunction "D+B_B6") (pintype "bidirectional"))
      (node (ref "R803") (pin "2") (pinfunction "2_2") (pintype "passive"))
    )
    (net (code "44") (name "Net-(CN801-D-A)") (class "Default")
      (node (ref "CN801") (pin "A7") (pinfunction "D-A_A7") (pintype "bidirectional"))
      (node (ref "CN801") (pin "B7") (pinfunction "D-B_B7") (pintype "bidirectional"))
      (node (ref "R804") (pin "2") (pinfunction "2_2") (pintype "passive"))
    )
    (net (code "45") (name "Net-(D401-A2)") (class "Default")
      (node (ref "D401") (pin "2") (pinfunction "A2_2") (pintype "passive"))
      (node (ref "MOTOR401") (pin "+") (pinfunction "+_+") (pintype "bidirectional"))
      (node (ref "R404") (pin "2") (pinfunction "2_2") (pintype "passive"))
    )
    (net (code "46") (name "Net-(DISPLAY301-F--Pad41)") (class "Default")
      (node (ref "DISPLAY301") (pin "41") (pinfunction "F-_41") (pintype "power_in"))
      (node (ref "DISPLAY301") (pin "42") (pinfunction "F-_42") (pintype "power_in"))
      (node (ref "DISPLAY301") (pin "43") (pinfunction "F-_43") (pintype "power_in"))
      (node (ref "R304") (pin "2") (pinfunction "2_2") (pintype "passive"))
    )
    (net (code "47") (name "Net-(DISPLAY301-OSCI)") (class "Default")
      (node (ref "C301") (pin "2") (pinfunction "2_2") (pintype "passive"))
      (node (ref "DISPLAY301") (pin "30") (pinfunction "OSCI_30") (pintype "input"))
      (node (ref "R302") (pin "1") (pinfunction "1_1") (pintype "passive"))
    )
    (net (code "48") (name "Net-(DISPLAY301-RST)") (class "Default")
      (node (ref "DISPLAY301") (pin "31") (pinfunction "RST_31") (pintype "input"))
      (node (ref "U301") (pin "13") (pinfunction "B1_13") (pintype "bidirectional"))
    )
    (net (code "49") (name "Net-(DISPLAY301-SCK)") (class "Default")
      (node (ref "DISPLAY301") (pin "34") (pinfunction "SCK_34") (pintype "input"))
      (node (ref "U301") (pin "10") (pinfunction "B4_10") (pintype "bidirectional"))
    )
    (net (code "50") (name "Net-(DISPLAY301-SISO)") (class "Default")
      (node (ref "DISPLAY301") (pin "32") (pinfunction "SISO_32") (pintype "bidirectional"))
      (node (ref "U301") (pin "12") (pinfunction "B2_12") (pintype "bidirectional"))
    )
    (net (code "51") (name "Net-(DISPLAY301-STB)") (class "Default")
      (node (ref "DISPLAY301") (pin "33") (pinfunction "STB_33") (pintype "input"))
      (node (ref "U301") (pin "11") (pinfunction "B3_11") (pintype "bidirectional"))
    )
    (net (code "52") (name "Net-(DISPLAY301-VDD2)") (class "Default")
      (node (ref "DISPLAY301") (pin "38") (pinfunction "VDD2_38") (pintype "power_in"))
      (node (ref "R303") (pin "1") (pinfunction "1_1") (pintype "passive"))
    )
    (net (code "53") (name "Net-(IC201A-GATE)") (class "Default")
      (node (ref "IC201") (pin "P$31") (pinfunction "GATE_P$31") (pintype "bidirectional"))
      (node (ref "Q202") (pin "1") (pinfunction "G_1") (pintype "passive"))
    )
    (net (code "54") (name "Net-(IC201A-SW)") (class "Default")
      (node (ref "IC201") (pin "P$37") (pinfunction "SW_P$37") (pintype "bidirectional"))
      (node (ref "L202") (pin "P$1") (pinfunction "1_P$1") (pintype "passive"))
    )
    (net (code "55") (name "Net-(IC201C-CLPROG)") (class "Default")
      (node (ref "C213") (pin "1") (pinfunction "1_1") (pintype "passive"))
      (node (ref "IC201") (pin "P$4") (pinfunction "CLPROG_P$4") (pintype "bidirectional"))
      (node (ref "R209") (pin "2") (pinfunction "2_2") (pintype "passive"))
    )
    (net (code "56") (name "Net-(IC201C-PROG)") (class "Default")
      (node (ref "IC201") (pin "P$29") (pinfunction "PROG_P$29") (pintype "bidirectional"))
      (node (ref "R208") (pin "2") (pinfunction "2_2") (pintype "passive"))
    )
    (net (code "57") (name "Net-(IC201E-FB)") (class "Default")
      (node (ref "C207") (pin "2") (pinfunction "2_2") (pintype "passive"))
      (node (ref "IC201") (pin "P$23") (pinfunction "FB_P$23") (pintype "bidirectional"))
      (node (ref "R204") (pin "1") (pinfunction "1_1") (pintype "passive"))
      (node (ref "R205") (pin "2") (pinfunction "2_2") (pintype "passive"))
    )
    (net (code "58") (name "Net-(IC201E-SW)") (class "Default")
      (node (ref "IC201") (pin "P$25") (pinfunction "SW_P$25") (pintype "bidirectional"))
      (node (ref "L203") (pin "P$1") (pinfunction "1_P$1") (pintype "passive"))
    )
    (net (code "59") (name "Net-(IC201F-FB3)") (class "Default")
      (node (ref "C214") (pin "1") (pinfunction "1_1") (pintype "passive"))
      (node (ref "C215") (pin "1") (pinfunction "1_1") (pintype "passive"))
      (node (ref "C218") (pin "2") (pinfunction "2_2") (pintype "passive"))
      (node (ref "IC201") (pin "P$11") (pinfunction "FB3_P$11") (pintype "bidirectional"))
      (node (ref "R214") (pin "1") (pinfunction "1_1") (pintype "passive"))
      (node (ref "R215") (pin "2") (pinfunction "2_2") (pintype "passive"))
    )
    (net (code "60") (name "Net-(IC201F-SWAB3)") (class "Default")
      (node (ref "IC201") (pin "P$13") (pinfunction "SWAB3_P$13") (pintype "bidirectional"))
      (node (ref "L205") (pin "P$2") (pinfunction "2_P$2") (pintype "passive"))
    )
    (net (code "61") (name "Net-(IC201F-SWCD3)") (class "Default")
      (node (ref "IC201") (pin "P$19") (pinfunction "SWCD3_P$19") (pintype "bidirectional"))
      (node (ref "L205") (pin "P$1") (pinfunction "1_P$1") (pintype "passive"))
    )
    (net (code "62") (name "Net-(IC201F-VC3)") (class "Default")
      (node (ref "C214") (pin "2") (pinfunction "2_2") (pintype "passive"))
      (node (ref "IC201") (pin "P$12") (pinfunction "VC3_P$12") (pintype "bidirectional"))
      (node (ref "R211") (pin "1") (pinfunction "1_1") (pintype "passive"))
    )
    (net (code "63") (name "Net-(IC201G-FB4)") (class "Default")
      (node (ref "C206") (pin "2") (pinfunction "2_2") (pintype "passive"))
      (node (ref "IC201") (pin "P$10") (pinfunction "FB4_P$10") (pintype "bidirectional"))
      (node (ref "R202") (pin "1") (pinfunction "1_1") (pintype "passive"))
      (node (ref "R203") (pin "2") (pinfunction "2_2") (pintype "passive"))
    )
    (net (code "64") (name "Net-(IC201G-SW4)") (class "Default")
      (node (ref "IC201") (pin "P$8") (pinfunction "SW4_P$8") (pintype "bidirectional"))
      (node (ref "L201") (pin "P$2") (pinfunction "2_P$2") (pintype "passive"))
    )
    (net (code "65") (name "Net-(IC202-FB)") (class "Default")
      (node (ref "C216") (pin "2") (pinfunction "2_2") (pintype "passive"))
      (node (ref "IC202") (pin "P3") (pinfunction "FB_P3") (pintype "bidirectional"))
      (node (ref "R212") (pin "1") (pinfunction "1_1") (pintype "passive"))
      (node (ref "R213") (pin "2") (pinfunction "2_2") (pintype "passive"))
    )
    (net (code "66") (name "Net-(IC202-SW)") (class "Default")
      (node (ref "IC202") (pin "P1") (pinfunction "SW_P1") (pintype "bidirectional"))
      (node (ref "L204") (pin "P$2") (pinfunction "P$2_P$2") (pintype "bidirectional"))
    )
    (net (code "67") (name "Net-(IC601-PTA7)") (class "Default")
      (node (ref "IC601") (pin "7") (pinfunction "PTA7_7") (pintype "bidirectional"))
      (node (ref "U601") (pin "25") (pinfunction "PTA3_25") (pintype "bidirectional"))
    )
    (net (code "68") (name "Net-(IC601-PTB0)") (class "Default")
      (node (ref "IC601") (pin "8") (pinfunction "PTB0_8") (pintype "bidirectional"))
      (node (ref "U601") (pin "22") (pinfunction "PTA0_22") (pintype "bidirectional"))
    )
    (net (code "69") (name "Net-(IC601-PTB1)") (class "Default")
      (node (ref "IC601") (pin "9") (pinfunction "PTB1_9") (pintype "bidirectional"))
      (node (ref "U601") (pin "24") (pinfunction "PTA2_24") (pintype "bidirectional"))
    )
    (net (code "70") (name "Net-(IC801-IO0)") (class "Default")
      (node (ref "IC801") (pin "4") (pinfunction "IO0_4") (pintype "bidirectional"))
      (node (ref "R806") (pin "2") (pinfunction "2_2") (pintype "passive"))
      (node (ref "SW806") (pin "D") (pinfunction "SW+_D") (pintype "bidirectional"))
    )
    (net (code "71") (name "Net-(IC801-IO1)") (class "Default")
      (node (ref "IC801") (pin "5") (pinfunction "IO1_5") (pintype "bidirectional"))
      (node (ref "R811") (pin "2") (pinfunction "2_2") (pintype "passive"))
      (node (ref "SW805") (pin "P$1") (pinfunction "P$1_P$1") (pintype "bidirectional"))
      (node (ref "SW805") (pin "P$2") (pinfunction "P$1_P$2") (pintype "bidirectional"))
    )
    (net (code "72") (name "Net-(IC801-IO2)") (class "Default")
      (node (ref "IC801") (pin "6") (pinfunction "IO2_6") (pintype "bidirectional"))
      (node (ref "R810") (pin "2") (pinfunction "2_2") (pintype "passive"))
      (node (ref "SW804") (pin "P$1") (pinfunction "P$1_P$1") (pintype "bidirectional"))
      (node (ref "SW804") (pin "P$2") (pinfunction "P$1_P$2") (pintype "bidirectional"))
    )
    (net (code "73") (name "Net-(IC801-IO3)") (class "Default")
      (node (ref "IC801") (pin "7") (pinfunction "IO3_7") (pintype "bidirectional"))
      (node (ref "R809") (pin "2") (pinfunction "2_2") (pintype "passive"))
      (node (ref "SW803") (pin "P$1") (pinfunction "P$1_P$1") (pintype "bidirectional"))
      (node (ref "SW803") (pin "P$2") (pinfunction "P$1_P$2") (pintype "bidirectional"))
    )
    (net (code "74") (name "Net-(IC801-IO4)") (class "Default")
      (node (ref "IC801") (pin "9") (pinfunction "IO4_9") (pintype "bidirectional"))
      (node (ref "R807") (pin "2") (pinfunction "2_2") (pintype "passive"))
      (node (ref "SW801") (pin "P$1") (pinfunction "P$1_P$1") (pintype "bidirectional"))
      (node (ref "SW801") (pin "P$2") (pinfunction "P$1_P$2") (pintype "bidirectional"))
    )
    (net (code "75") (name "Net-(IC801-IO5)") (class "Default")
      (node (ref "IC801") (pin "10") (pinfunction "IO5_10") (pintype "bidirectional"))
      (node (ref "R808") (pin "2") (pinfunction "2_2") (pintype "passive"))
      (node (ref "SW802") (pin "P$1") (pinfunction "P$1_P$1") (pintype "bidirectional"))
      (node (ref "SW802") (pin "P$2") (pinfunction "P$1_P$2") (pintype "bidirectional"))
    )
    (net (code "76") (name "Net-(LED801-PadDIN)") (class "Default")
      (node (ref "LED801") (pin "DIN") (pinfunction "DIN_DIN") (pintype "bidirectional"))
      (node (ref "R812") (pin "1") (pinfunction "1_1") (pintype "passive"))
    )
    (net (code "77") (name "Net-(LED801-PadDOUT)") (class "Default")
      (node (ref "LED801") (pin "DOUT") (pinfunction "DOUT_DOUT") (pintype "bidirectional"))
      (node (ref "LED802") (pin "DIN") (pinfunction "DIN_DIN") (pintype "bidirectional"))
    )
    (net (code "78") (name "Net-(LED802-PadDOUT)") (class "Default")
      (node (ref "LED802") (pin "DOUT") (pinfunction "DOUT_DOUT") (pintype "bidirectional"))
      (node (ref "LED803") (pin "DIN") (pinfunction "DIN_DIN") (pintype "bidirectional"))
    )
    (net (code "79") (name "Net-(LED803-PadDOUT)") (class "Default")
      (node (ref "LED803") (pin "DOUT") (pinfunction "DOUT_DOUT") (pintype "bidirectional"))
      (node (ref "LED804") (pin "DIN") (pinfunction "DIN_DIN") (pintype "bidirectional"))
    )
    (net (code "80") (name "Net-(LED804-PadDOUT)") (class "Default")
      (node (ref "LED804") (pin "DOUT") (pinfunction "DOUT_DOUT") (pintype "bidirectional"))
      (node (ref "LED805") (pin "DIN") (pinfunction "DIN_DIN") (pintype "bidirectional"))
    )
    (net (code "81") (name "Net-(MOD401-SCL1)") (class "Default")
      (node (ref "MOD401") (pin "P$11") (pinfunction "SCL1_P$11") (pintype "bidirectional"))
      (node (ref "R403") (pin "1") (pinfunction "1_1") (pintype "passive"))
    )
    (net (code "82") (name "Net-(MOD401-SDA1)") (class "Default")
      (node (ref "MOD401") (pin "P$12") (pinfunction "SDA1_P$12") (pintype "bidirectional"))
      (node (ref "R402") (pin "1") (pinfunction "1_1") (pintype "passive"))
    )
    (net (code "83") (name "Net-(MOD401-SWCLK)") (class "Default")
      (node (ref "JP401") (pin "2") (pinfunction "2_2") (pintype "passive"))
      (node (ref "MOD401") (pin "P$36") (pinfunction "SWCLK_P$36") (pintype "bidirectional"))
      (node (ref "R401") (pin "2") (pinfunction "2_2") (pintype "passive"))
    )
    (net (code "84") (name "Net-(MOD401-SWDIO{slash}RST)") (class "Default")
      (node (ref "JP401") (pin "3") (pinfunction "3_3") (pintype "passive"))
      (node (ref "MOD401") (pin "P$35") (pinfunction "SWDIO/RST_P$35") (pintype "bidirectional"))
    )
    (net (code "85") (name "Net-(MOD401-XL1)") (class "Default")
      (node (ref "C404") (pin "1") (pinfunction "1_1") (pintype "passive"))
      (node (ref "MOD401") (pin "P$10") (pinfunction "XL1_P$10") (pintype "bidirectional"))
      (node (ref "Q401") (pin "1") (pinfunction "1_1") (pintype "passive"))
    )
    (net (code "86") (name "Net-(MOD401-XL2)") (class "Default")
      (node (ref "C403") (pin "1") (pinfunction "1_1") (pintype "passive"))
      (node (ref "MOD401") (pin "P$9") (pinfunction "XL2_P$9") (pintype "bidirectional"))
      (node (ref "Q401") (pin "2") (pinfunction "2_2") (pintype "passive"))
    )
    (net (code "87") (name "Net-(Q201-D)") (class "Default")
      (node (ref "C202") (pin "1") (pinfunction "1_1") (pintype "passive"))
      (node (ref "IC201") (pin "P$35") (pinfunction "VBUS_P$35") (pintype "bidirectional"))
      (node (ref "IC201") (pin "P$36") (pinfunction "VBUS_P$36") (pintype "bidirectional"))
      (node (ref "Q201") (pin "3") (pinfunction "D_3") (pintype "passive"))
    )
    (net (code "88") (name "Net-(Q201-G)") (class "Default")
      (node (ref "C201") (pin "2") (pinfunction "2_2") (pintype "passive"))
      (node (ref "Q201") (pin "1") (pinfunction "G_1") (pintype "passive"))
      (node (ref "R201") (pin "2") (pinfunction "2_2") (pintype "passive"))
    )
    (net (code "89") (name "Net-(Q402-D)") (class "Default")
      (node (ref "Q402") (pin "3") (pinfunction "D_3") (pintype "bidirectional"))
      (node (ref "R404") (pin "1") (pinfunction "1_1") (pintype "passive"))
    )
    (net (code "90") (name "Net-(U601-EXTAL32)") (class "Default")
      (node (ref "Q601") (pin "1") (pinfunction "1_1") (pintype "passive"))
      (node (ref "U601") (pin "20") (pinfunction "EXTAL32_20") (pintype "bidirectional"))
    )
    (net (code "91") (name "Net-(U601-PTA18)") (class "Default")
      (node (ref "U601") (pin "32") (pinfunction "PTA18_32") (pintype "bidirectional"))
      (node (ref "Y601") (pin "3") (pinfunction "2_3") (pintype "passive"))
    )
    (net (code "92") (name "Net-(U601-PTA19)") (class "Default")
      (node (ref "U601") (pin "33") (pinfunction "PTA19_33") (pintype "bidirectional"))
      (node (ref "Y601") (pin "1") (pinfunction "1_1") (pintype "passive"))
    )
    (net (code "93") (name "Net-(U601-VDDA)") (class "Default")
      (node (ref "C606") (pin "1") (pinfunction "1_1") (pintype "passive"))
      (node (ref "L602") (pin "1") (pinfunction "1_1") (pintype "passive"))
      (node (ref "R601") (pin "2") (pinfunction "2_2") (pintype "passive"))
      (node (ref "U601") (pin "13") (pinfunction "VDDA_13") (pintype "bidirectional"))
    )
    (net (code "94") (name "Net-(U601-VREFH)") (class "Default")
      (node (ref "C607") (pin "1") (pinfunction "1_1") (pintype "passive"))
      (node (ref "R601") (pin "1") (pinfunction "1_1") (pintype "passive"))
      (node (ref "U601") (pin "14") (pinfunction "VREFH_14") (pintype "bidirectional"))
    )
    (net (code "95") (name "Net-(U601-VREF_OUT)") (class "Default")
      (node (ref "C608") (pin "1") (pinfunction "1_1") (pintype "passive"))
      (node (ref "U601") (pin "17") (pinfunction "VREF_OUT_17") (pintype "bidirectional"))
    )
    (net (code "96") (name "Net-(U601-XTAL32)") (class "Default")
      (node (ref "Q601") (pin "2") (pinfunction "2_2") (pintype "passive"))
      (node (ref "U601") (pin "19") (pinfunction "XTAL32_19") (pintype "bidirectional"))
    )
    (net (code "97") (name "PROGRAM") (class "Default")
      (node (ref "CN701") (pin "P$1") (pinfunction "P$1_P$1") (pintype "bidirectional"))
      (node (ref "IC601") (pin "10") (pinfunction "PTB2_10") (pintype "bidirectional"))
    )
    (net (code "98") (name "PROGRAM'") (class "Default")
      (node (ref "JP701") (pin "P$20") (pinfunction "P$1_P$20") (pintype "bidirectional"))
      (node (ref "R801") (pin "2") (pinfunction "2_2") (pintype "passive"))
    )
    (net (code "99") (name "REG_MODE") (class "Default")
      (node (ref "IC201") (pin "P$9") (pinfunction "MODE_P$9") (pintype "bidirectional"))
      (node (ref "R210") (pin "2") (pinfunction "2_2") (pintype "passive"))
    )
    (net (code "100") (name "RESET") (class "Default")
      (node (ref "IC601") (pin "13") (pinfunction "PTB5_13") (pintype "bidirectional"))
      (node (ref "IC601") (pin "4") (pinfunction "PTA4_4") (pintype "bidirectional"))
      (node (ref "U601") (pin "34") (pinfunction "RESET_B_34") (pintype "bidirectional"))
    )
    (net (code "101") (name "SCK") (class "Default")
      (node (ref "CN502") (pin "PAD4") (pinfunction "P$1_PAD4") (pintype "bidirectional"))
      (node (ref "CN503") (pin "PAD4") (pinfunction "P$1_PAD4") (pintype "bidirectional"))
      (node (ref "CN505") (pin "PAD4") (pinfunction "P$1_PAD4") (pintype "bidirectional"))
      (node (ref "CN507") (pin "PAD4") (pinfunction "P$1_PAD4") (pintype "bidirectional"))
      (node (ref "U601") (pin "50") (pinfunction "PTC5_50") (pintype "bidirectional"))
    )
    (net (code "102") (name "SCL") (class "Default")
      (node (ref "CN701") (pin "P$8") (pinfunction "P$1_P$8") (pintype "bidirectional"))
      (node (ref "IC501") (pin "14") (pinfunction "SCL_14") (pintype "input"))
      (node (ref "MOD401") (pin "P$26") (pinfunction "SCL_P$26") (pintype "bidirectional"))
      (node (ref "MOD402") (pin "P$3") (pinfunction "SCLS_P$3") (pintype "bidirectional"))
      (node (ref "R602") (pin "1") (pinfunction "1_1") (pintype "passive"))
      (node (ref "U601") (pin "37") (pinfunction "PTB2_37") (pintype "bidirectional"))
    )
    (net (code "103") (name "SCL'") (class "Default")
      (node (ref "IC801") (pin "14") (pinfunction "SCL_14") (pintype "input"))
      (node (ref "JP701") (pin "P$13") (pinfunction "P$1_P$13") (pintype "bidirectional"))
    )
    (net (code "104") (name "SCL1") (class "Default")
      (node (ref "CN502") (pin "PAD6") (pinfunction "P$1_PAD6") (pintype "bidirectional"))
      (node (ref "CN503") (pin "PAD6") (pinfunction "P$1_PAD6") (pintype "bidirectional"))
      (node (ref "CN505") (pin "PAD6") (pinfunction "P$1_PAD6") (pintype "bidirectional"))
      (node (ref "CN507") (pin "PAD6") (pinfunction "P$1_PAD6") (pintype "bidirectional"))
      (node (ref "R605") (pin "1") (pinfunction "1_1") (pintype "passive"))
      (node (ref "U601") (pin "55") (pinfunction "PTC10_55") (pintype "bidirectional"))
    )
    (net (code "105") (name "SDA") (class "Default")
      (node (ref "CN701") (pin "P$7") (pinfunction "P$1_P$7") (pintype "bidirectional"))
      (node (ref "IC501") (pin "15") (pinfunction "SDA_15") (pintype "bidirectional"))
      (node (ref "MOD401") (pin "P$28") (pinfunction "SDA_P$28") (pintype "bidirectional"))
      (node (ref "MOD402") (pin "P$2") (pinfunction "SDAS_P$2") (pintype "bidirectional"))
      (node (ref "R603") (pin "1") (pinfunction "1_1") (pintype "passive"))
      (node (ref "U601") (pin "38") (pinfunction "PTB3_38") (pintype "bidirectional"))
    )
    (net (code "106") (name "SDA'") (class "Default")
      (node (ref "IC801") (pin "15") (pinfunction "SDA_15") (pintype "bidirectional"))
      (node (ref "JP701") (pin "P$14") (pinfunction "P$1_P$14") (pintype "bidirectional"))
    )
    (net (code "107") (name "SDA1") (class "Default")
      (node (ref "CN502") (pin "PAD5") (pinfunction "P$1_PAD5") (pintype "bidirectional"))
      (node (ref "CN503") (pin "PAD5") (pinfunction "P$1_PAD5") (pintype "bidirectional"))
      (node (ref "CN505") (pin "PAD5") (pinfunction "P$1_PAD5") (pintype "bidirectional"))
      (node (ref "CN507") (pin "PAD5") (pinfunction "P$1_PAD5") (pintype "bidirectional"))
      (node (ref "R604") (pin "1") (pinfunction "1_1") (pintype "passive"))
      (node (ref "U601") (pin "56") (pinfunction "PTC11_56") (pintype "bidirectional"))
    )
    (net (code "108") (name "SISO") (class "Default")
      (node (ref "U301") (pin "3") (pinfunction "A2_3") (pintype "bidirectional"))
      (node (ref "U601") (pin "59") (pinfunction "PTD2_59") (pintype "bidirectional"))
    )
    (net (code "109") (name "SS_MOD0") (class "Default")
      (node (ref "CN502") (pin "PAD1") (pinfunction "P$1_PAD1") (pintype "bidirectional"))
      (node (ref "IC501") (pin "4") (pinfunction "IO0_4") (pintype "bidirectional"))
    )
    (net (code "110") (name "SS_MOD1") (class "Default")
      (node (ref "CN503") (pin "PAD1") (pinfunction "P$1_PAD1") (pintype "bidirectional"))
      (node (ref "IC501") (pin "6") (pinfunction "IO2_6") (pintype "bidirectional"))
    )
    (net (code "111") (name "SS_MOD2") (class "Default")
      (node (ref "CN505") (pin "PAD1") (pinfunction "P$1_PAD1") (pintype "bidirectional"))
      (node (ref "IC501") (pin "9") (pinfunction "IO4_9") (pintype "bidirectional"))
    )
    (net (code "112") (name "SS_MOD3") (class "Default")
      (node (ref "CN507") (pin "PAD1") (pinfunction "P$1_PAD1") (pintype "bidirectional"))
      (node (ref "IC501") (pin "11") (pinfunction "IO6_11") (pintype "bidirectional"))
    )
    (net (code "113") (name "STB") (class "Default")
      (node (ref "U301") (pin "4") (pinfunction "A3_4") (pintype "bidirectional"))
      (node (ref "U601") (pin "2") (pinfunction "PTE1_2") (pintype "bidirectional"))
    )
    (net (code "114") (name "USB+") (class "Default")
      (node (ref "CN701") (pin "P$3") (pinfunction "P$1_P$3") (pintype "bidirectional"))
      (node (ref "U601") (pin "5") (pinfunction "USB0_DP_5") (pintype "bidirectional"))
    )
    (net (code "115") (name "USB+'") (class "Default")
      (node (ref "JP701") (pin "P$18") (pinfunction "P$1_P$18") (pintype "bidirectional"))
      (node (ref "R803") (pin "1") (pinfunction "1_1") (pintype "passive"))
    )
    (net (code "116") (name "USB-") (class "Default")
      (node (ref "CN701") (pin "P$2") (pinfunction "P$1_P$2") (pintype "bidirectional"))
      (node (ref "U601") (pin "6") (pinfunction "USB0_DM_6") (pintype "bidirectional"))
    )
    (net (code "117") (name "USB-'") (class "Default")
      (node (ref "JP701") (pin "P$19") (pinfunction "P$1_P$19") (pintype "bidirectional"))
      (node (ref "R804") (pin "1") (pinfunction "1_1") (pintype "passive"))
    )
    (net (code "118") (name "USB_ID") (class "Default")
      (node (ref "IC601") (pin "6") (pinfunction "PTA6_6") (pintype "bidirectional"))
      (node (ref "U601") (pin "23") (pinfunction "PTA1_23") (pintype "bidirectional"))
    )
    (net (code "119") (name "V+") (class "Default")
      (node (ref "C203") (pin "1") (pinfunction "1_1") (pintype "passive"))
      (node (ref "C204") (pin "1") (pinfunction "1_1") (pintype "passive"))
      (node (ref "C208") (pin "1") (pinfunction "1_1") (pintype "passive"))
      (node (ref "C211") (pin "1") (pinfunction "1_1") (pintype "passive"))
      (node (ref "IC201") (pin "P$14") (pinfunction "VIN3_P$14") (pintype "bidirectional"))
      (node (ref "IC201") (pin "P$15") (pinfunction "VIN3_P$15") (pintype "bidirectional"))
      (node (ref "IC201") (pin "P$22") (pinfunction "VIN4_P$22") (pintype "bidirectional"))
      (node (ref "IC201") (pin "P$24") (pinfunction "VIN_P$24") (pintype "bidirectional"))
      (node (ref "IC201") (pin "P$34") (pinfunction "VOUT_P$34") (pintype "bidirectional"))
      (node (ref "L201") (pin "P$1") (pinfunction "1_P$1") (pintype "passive"))
      (node (ref "L202") (pin "P$3") (pinfunction "2_P$3") (pintype "passive"))
      (node (ref "Q202") (pin "2") (pinfunction "S_2") (pintype "passive"))
    )
    (net (code "120") (name "VCC{slash}2") (class "Default")
      (node (ref "C207") (pin "1") (pinfunction "1_1") (pintype "passive"))
      (node (ref "C210") (pin "1") (pinfunction "1_1") (pintype "passive"))
      (node (ref "C401") (pin "1") (pinfunction "1_1") (pintype "passive"))
      (node (ref "C402") (pin "1") (pinfunction "1_1") (pintype "passive"))
      (node (ref "C601") (pin "1") (pinfunction "1_1") (pintype "passive"))
      (node (ref "C602") (pin "1") (pinfunction "1_1") (pintype "passive"))
      (node (ref "C603") (pin "1") (pinfunction "1_1") (pintype "passive"))
      (node (ref "C604") (pin "1") (pinfunction "1_1") (pintype "passive"))
      (node (ref "C605") (pin "1") (pinfunction "1_1") (pintype "passive"))
      (node (ref "CN701") (pin "P$16") (pinfunction "P$1_P$16") (pintype "bidirectional"))
      (node (ref "CN701") (pin "P$17") (pinfunction "P$1_P$17") (pintype "bidirectional"))
      (node (ref "D401") (pin "3") (pinfunction "CC_3") (pintype "passive"))
      (node (ref "IC501") (pin "16") (pinfunction "VDD_16") (pintype "power_in"))
      (node (ref "IC601") (pin "1") (pinfunction "VDD_1") (pintype "bidirectional"))
      (node (ref "JP401") (pin "1") (pinfunction "1_1") (pintype "passive"))
      (node (ref "L203") (pin "P$2") (pinfunction "2_P$2") (pintype "passive"))
      (node (ref "L602") (pin "2") (pinfunction "2_2") (pintype "passive"))
      (node (ref "MOD401") (pin "P$14") (pinfunction "VDD_P$14") (pintype "bidirectional"))
      (node (ref "MOD401") (pin "P$3") (pinfunction "AVDD_P$3") (pintype "bidirectional"))
      (node (ref "MOD402") (pin "P$1") (pinfunction "VDD_P$1") (pintype "bidirectional"))
      (node (ref "MOTOR401") (pin "-") (pinfunction "-_-") (pintype "bidirectional"))
      (node (ref "R204") (pin "2") (pinfunction "2_2") (pintype "passive"))
      (node (ref "R301") (pin "2") (pinfunction "2_2") (pintype "passive"))
      (node (ref "R602") (pin "2") (pinfunction "2_2") (pintype "passive"))
      (node (ref "R603") (pin "2") (pinfunction "2_2") (pintype "passive"))
      (node (ref "R604") (pin "2") (pinfunction "2_2") (pintype "passive"))
      (node (ref "R605") (pin "2") (pinfunction "2_2") (pintype "passive"))
      (node (ref "U301") (pin "1") (pinfunction "VCCA_1") (pintype "bidirectional"))
      (node (ref "U301") (pin "8") (pinfunction "OE_8") (pintype "bidirectional"))
      (node (ref "U601") (pin "3") (pinfunction "VDD_3") (pintype "bidirectional"))
      (node (ref "U601") (pin "30") (pinfunction "VDD_30") (pintype "bidirectional"))
      (node (ref "U601") (pin "48") (pinfunction "VDD_48") (pintype "bidirectional"))
      (node (ref "U601") (pin "7") (pinfunction "VOUT33_7") (pintype "bidirectional"))
    )
    (net (code "121") (name "VCC{slash}2'") (class "Default")
      (node (ref "C801") (pin "1") (pinfunction "1_1") (pintype "passive"))
      (node (ref "C802") (pin "1") (pinfunction "1_1") (pintype "passive"))
      (node (ref "C803") (pin "1") (pinfunction "1_1") (pintype "passive"))
      (node (ref "C804") (pin "1") (pinfunction "1_1") (pintype "passive"))
      (node (ref "C805") (pin "1") (pinfunction "1_1") (pintype "passive"))
      (node (ref "C806") (pin "1") (pinfunction "1_1") (pintype "passive"))
      (node (ref "IC801") (pin "16") (pinfunction "VDD_16") (pintype "power_in"))
      (node (ref "IC801") (pin "3") (pinfunction "A2_3") (pintype "input"))
      (node (ref "JP701") (pin "P$4") (pinfunction "P$1_P$4") (pintype "bidirectional"))
      (node (ref "JP701") (pin "P$5") (pinfunction "P$1_P$5") (pintype "bidirectional"))
      (node (ref "LED801") (pin "VCC") (pinfunction "VDD_VCC") (pintype "bidirectional"))
      (node (ref "LED802") (pin "VCC") (pinfunction "VDD_VCC") (pintype "bidirectional"))
      (node (ref "LED803") (pin "VCC") (pinfunction "VDD_VCC") (pintype "bidirectional"))
      (node (ref "LED804") (pin "VCC") (pinfunction "VDD_VCC") (pintype "bidirectional"))
      (node (ref "LED805") (pin "VCC") (pinfunction "VDD_VCC") (pintype "bidirectional"))
      (node (ref "SW801") (pin "P$3") (pinfunction "P$2_P$3") (pintype "bidirectional"))
      (node (ref "SW801") (pin "P$4") (pinfunction "P$2_P$4") (pintype "bidirectional"))
      (node (ref "SW802") (pin "P$3") (pinfunction "P$2_P$3") (pintype "bidirectional"))
      (node (ref "SW802") (pin "P$4") (pinfunction "P$2_P$4") (pintype "bidirectional"))
      (node (ref "SW803") (pin "P$3") (pinfunction "P$2_P$3") (pintype "bidirectional"))
      (node (ref "SW803") (pin "P$4") (pinfunction "P$2_P$4") (pintype "bidirectional"))
      (node (ref "SW804") (pin "P$3") (pinfunction "P$2_P$3") (pintype "bidirectional"))
      (node (ref "SW804") (pin "P$4") (pinfunction "P$2_P$4") (pintype "bidirectional"))
      (node (ref "SW805") (pin "P$3") (pinfunction "P$2_P$3") (pintype "bidirectional"))
      (node (ref "SW805") (pin "P$4") (pinfunction "P$2_P$4") (pintype "bidirectional"))
      (node (ref "SW806") (pin "E") (pinfunction "SW-_E") (pintype "bidirectional"))
    )
    (net (code "122") (name "VDISPLAY") (class "Default")
      (node (ref "C216") (pin "1") (pinfunction "1_1") (pintype "passive"))
      (node (ref "C217") (pin "1") (pinfunction "1_1") (pintype "passive"))
      (node (ref "IC202") (pin "P5") (pinfunction "VOUT_P5") (pintype "bidirectional"))
      (node (ref "R212") (pin "2") (pinfunction "2_2") (pintype "passive"))
      (node (ref "R303") (pin "2") (pinfunction "2_2") (pintype "passive"))
    )
    (net (code "123") (name "VIBES") (class "Default")
      (node (ref "Q402") (pin "1") (pinfunction "G_1") (pintype "bidirectional"))
      (node (ref "R405") (pin "2") (pinfunction "2_2") (pintype "passive"))
      (node (ref "U601") (pin "61") (pinfunction "PTD4_61") (pintype "bidirectional"))
    )
    (net (code "124") (name "VUSB") (class "Default")
      (node (ref "C201") (pin "1") (pinfunction "1_1") (pintype "passive"))
      (node (ref "CN701") (pin "P$4") (pinfunction "P$1_P$4") (pintype "bidirectional"))
      (node (ref "CN701") (pin "P$5") (pinfunction "P$1_P$5") (pintype "bidirectional"))
      (node (ref "CN701") (pin "P$6") (pinfunction "P$1_P$6") (pintype "bidirectional"))
      (node (ref "Q201") (pin "2") (pinfunction "S_2") (pintype "passive"))
    )
    (net (code "125") (name "VUSB'") (class "Default")
      (node (ref "CN801") (pin "A4") (pinfunction "VUSB_A4") (pintype "bidirectional"))
      (node (ref "CN801") (pin "A9") (pinfunction "VUSB_A9") (pintype "bidirectional"))
      (node (ref "CN801") (pin "B4") (pinfunction "VUSB_B4") (pintype "bidirectional"))
      (node (ref "CN801") (pin "B9") (pinfunction "VUSB_B9") (pintype "bidirectional"))
      (node (ref "JP701") (pin "P$15") (pinfunction "P$1_P$15") (pintype "bidirectional"))
      (node (ref "JP701") (pin "P$16") (pinfunction "P$1_P$16") (pintype "bidirectional"))
      (node (ref "JP701") (pin "P$17") (pinfunction "P$1_P$17") (pintype "bidirectional"))
    )
    (net (code "126") (name "WAKE_BLE") (class "Default")
      (node (ref "R403") (pin "2") (pinfunction "2_2") (pintype "passive"))
      (node (ref "U601") (pin "28") (pinfunction "PTA12_28") (pintype "bidirectional"))
    )
    (net (code "127") (name "unconnected-(D401-A1-Pad1)") (class "Default")
      (node (ref "D401") (pin "1") (pinfunction "A1_1") (pintype "passive"))
    )
    (net (code "128") (name "unconnected-(DISPLAY301-HOSC1-Pad27)") (class "Default")
      (node (ref "DISPLAY301") (pin "27") (pinfunction "HOSC1_27") (pintype "bidirectional"))
    )
    (net (code "129") (name "unconnected-(DISPLAY301-HOSC2-Pad26)") (class "Default")
      (node (ref "DISPLAY301") (pin "26") (pinfunction "HOSC2_26") (pintype "bidirectional"))
    )
    (net (code "130") (name "unconnected-(IC201C-~{FAULT}-PadP$38)") (class "Default")
      (node (ref "IC201") (pin "P$38") (pinfunction "~{FAULT}_P$38") (pintype "bidirectional"))
    )
    (net (code "131") (name "unconnected-(IC801-IO6-Pad11)") (class "Default")
      (node (ref "IC801") (pin "11") (pinfunction "IO6_11") (pintype "bidirectional"))
    )
    (net (code "132") (name "unconnected-(IC801-IO7-Pad12)") (class "Default")
      (node (ref "IC801") (pin "12") (pinfunction "IO7_12") (pintype "bidirectional"))
    )
    (net (code "133") (name "unconnected-(JP501J-P$1-PadSCL)") (class "Default")
      (node (ref "JP501") (pin "SCL") (pinfunction "P$1_SCL") (pintype "bidirectional"))
    )
    (net (code "134") (name "unconnected-(JP502J-P$1-PadSCL)") (class "Default")
      (node (ref "JP502") (pin "SCL") (pinfunction "P$1_SCL") (pintype "bidirectional"))
    )
    (net (code "135") (name "unconnected-(JP503J-P$1-PadSCL)") (class "Default")
      (node (ref "JP503") (pin "SCL") (pinfunction "P$1_SCL") (pintype "bidirectional"))
    )
    (net (code "136") (name "unconnected-(JP504J-P$1-PadSCL)") (class "Default")
      (node (ref "JP504") (pin "SCL") (pinfunction "P$1_SCL") (pintype "bidirectional"))
    )
    (net (code "137") (name "unconnected-(LED805-PadDOUT)") (class "Default")
      (node (ref "LED805") (pin "DOUT") (pinfunction "DOUT_DOUT") (pintype "bidirectional"))
    )
    (net (code "138") (name "unconnected-(MOD401-CLK-PadP$8)") (class "Default")
      (node (ref "MOD401") (pin "P$8") (pinfunction "CLK_P$8") (pintype "bidirectional"))
    )
    (net (code "139") (name "unconnected-(MOD401-DCC-PadP$15)") (class "Default")
      (node (ref "MOD401") (pin "P$15") (pinfunction "DCC_P$15") (pintype "bidirectional"))
    )
    (net (code "140") (name "unconnected-(MOD401-DEC2-PadP$41)") (class "Default")
      (node (ref "MOD401") (pin "P$41") (pinfunction "DEC2_P$41") (pintype "bidirectional"))
    )
    (net (code "141") (name "unconnected-(MOD401-MISO-PadP$5)") (class "Default")
      (node (ref "MOD401") (pin "P$5") (pinfunction "MISO_P$5") (pintype "bidirectional"))
    )
    (net (code "142") (name "unconnected-(MOD401-MOSI-PadP$40)") (class "Default")
      (node (ref "MOD401") (pin "P$40") (pinfunction "MOSI_P$40") (pintype "bidirectional"))
    )
    (net (code "143") (name "unconnected-(MOD401-RX-PadP$29)") (class "Default")
      (node (ref "MOD401") (pin "P$29") (pinfunction "RX_P$29") (pintype "bidirectional"))
    )
    (net (code "144") (name "unconnected-(MOD401-TX-PadP$27)") (class "Default")
      (node (ref "MOD401") (pin "P$27") (pinfunction "TX_P$27") (pintype "bidirectional"))
    )
    (net (code "145") (name "unconnected-(U601-ADC0_DM0-Pad10)") (class "Default")
      (node (ref "U601") (pin "10") (pinfunction "ADC0_DM0_10") (pintype "bidirectional"))
    )
    (net (code "146") (name "unconnected-(U601-ADC0_DM3-Pad12)") (class "Default")
      (node (ref "U601") (pin "12") (pinfunction "ADC0_DM3_12") (pintype "bidirectional"))
    )
    (net (code "147") (name "unconnected-(U601-ADC0_DP0-Pad9)") (class "Default")
      (node (ref "U601") (pin "9") (pinfunction "ADC0_DP0_9") (pintype "bidirectional"))
    )
    (net (code "148") (name "unconnected-(U601-PTC4-Pad49)") (class "Default")
      (node (ref "U601") (pin "49") (pinfunction "PTC4_49") (pintype "bidirectional"))
    )
    (net (code "149") (name "unconnected-(U601-PTC8-Pad53)") (class "Default")
      (node (ref "U601") (pin "53") (pinfunction "PTC8_53") (pintype "bidirectional"))
    )
    (net (code "150") (name "unconnected-(U601-PTC9-Pad54)") (class "Default")
      (node (ref "U601") (pin "54") (pinfunction "PTC9_54") (pintype "bidirectional"))
    )
    (net (code "151") (name "unconnected-(U601-PTD0-Pad57)") (class "Default")
      (node (ref "U601") (pin "57") (pinfunction "PTD0_57") (pintype "bidirectional"))
    )
    (net (code "152") (name "unconnected-(U601-VREGIN-Pad8)") (class "Default")
      (node (ref "U601") (pin "8") (pinfunction "VREGIN_8") (pintype "bidirectional"))
    )
  )
)
